# S140032_EMS_10HP_DS.net
KiCad netlist of a schematic drawn in EAGLE
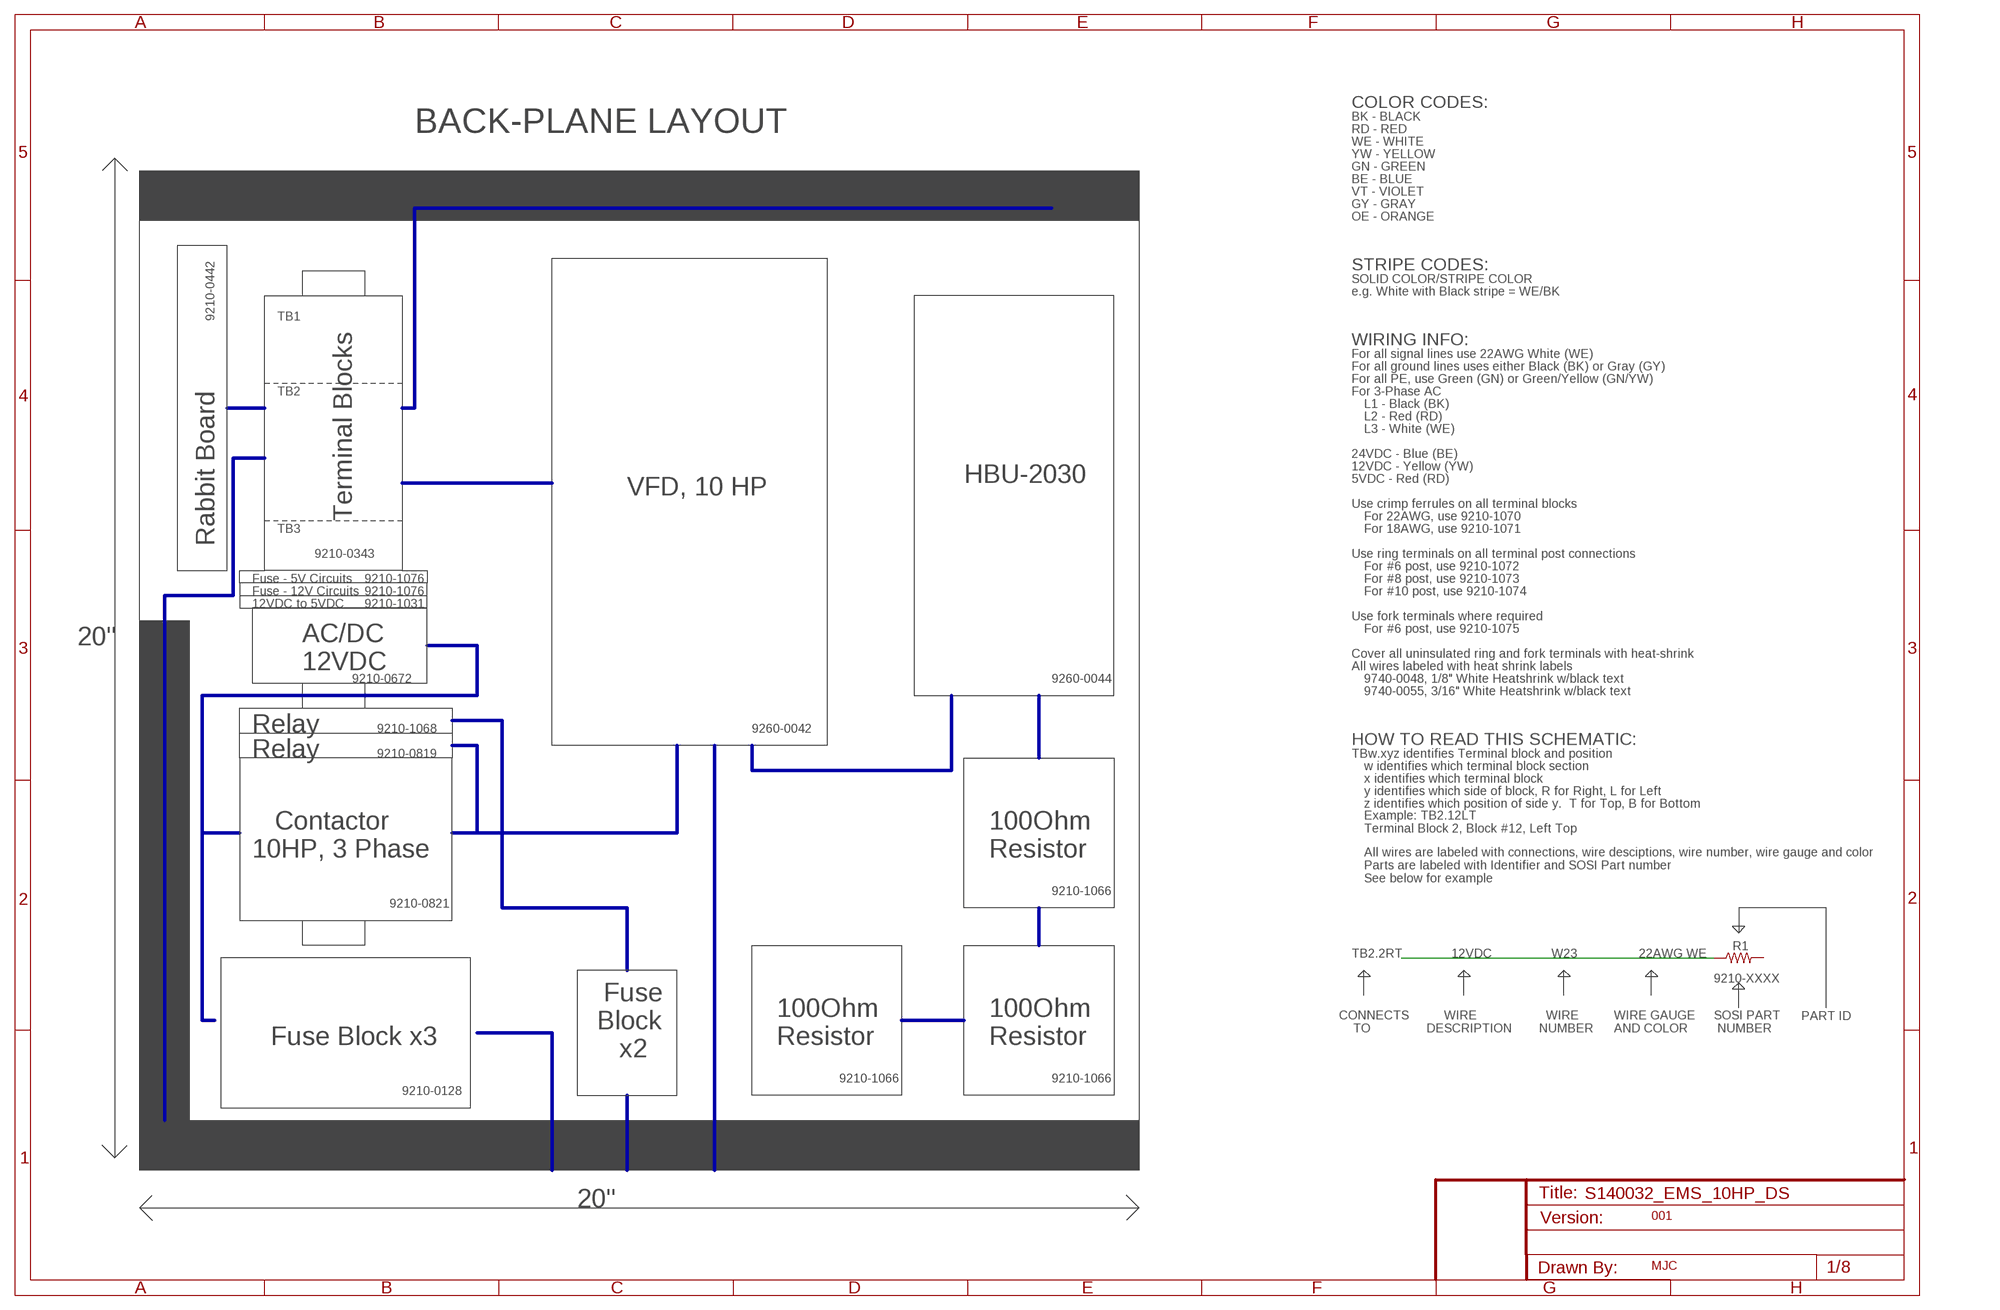
[diagram p0: schematic, sheet 1]
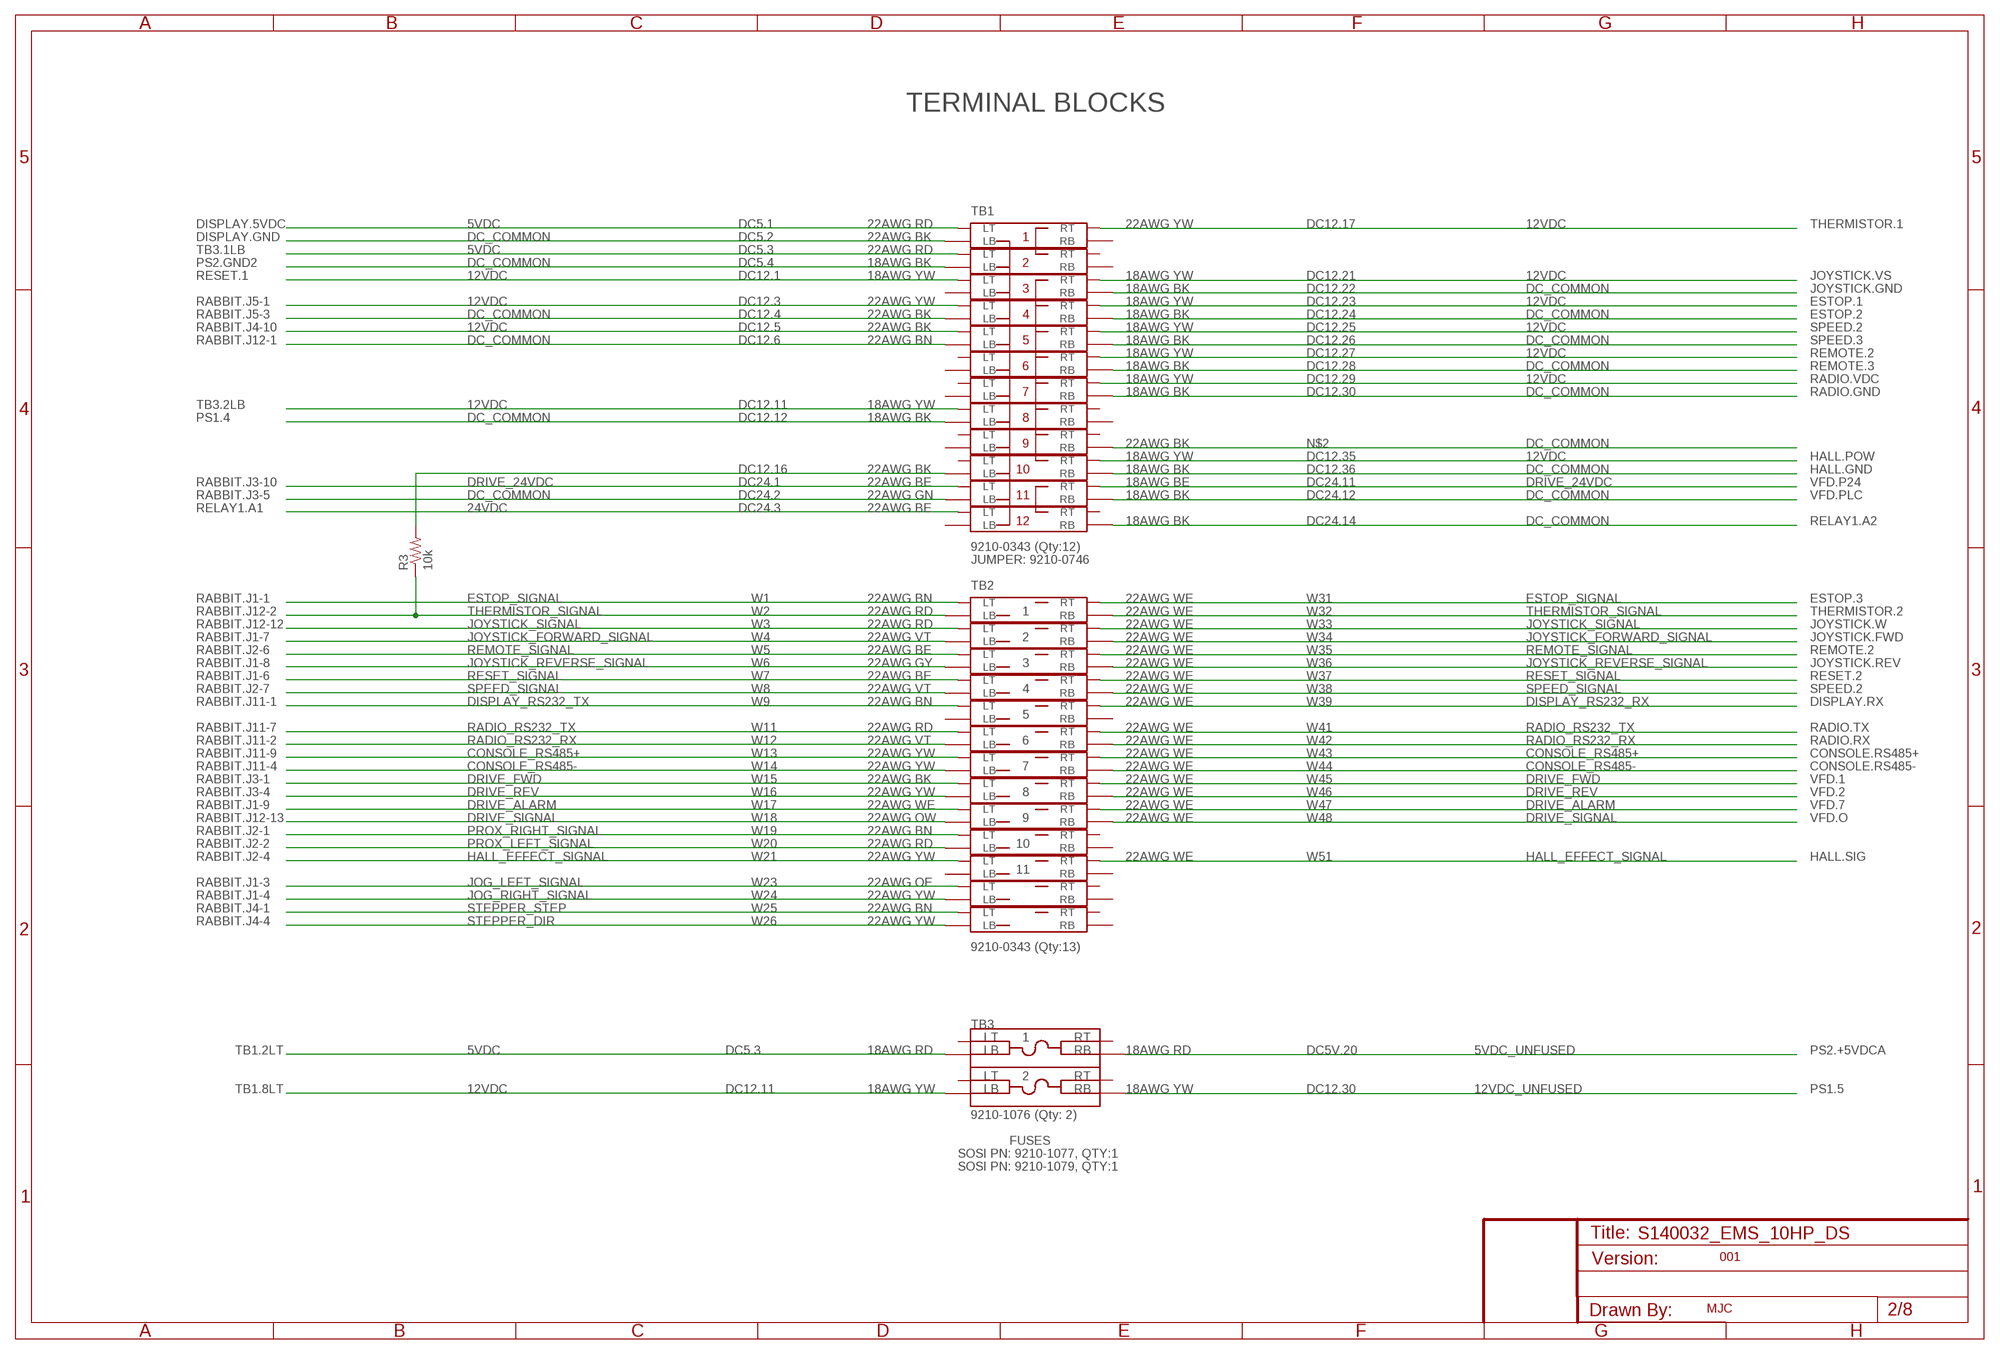
[diagram p1: schematic, sheet 2]
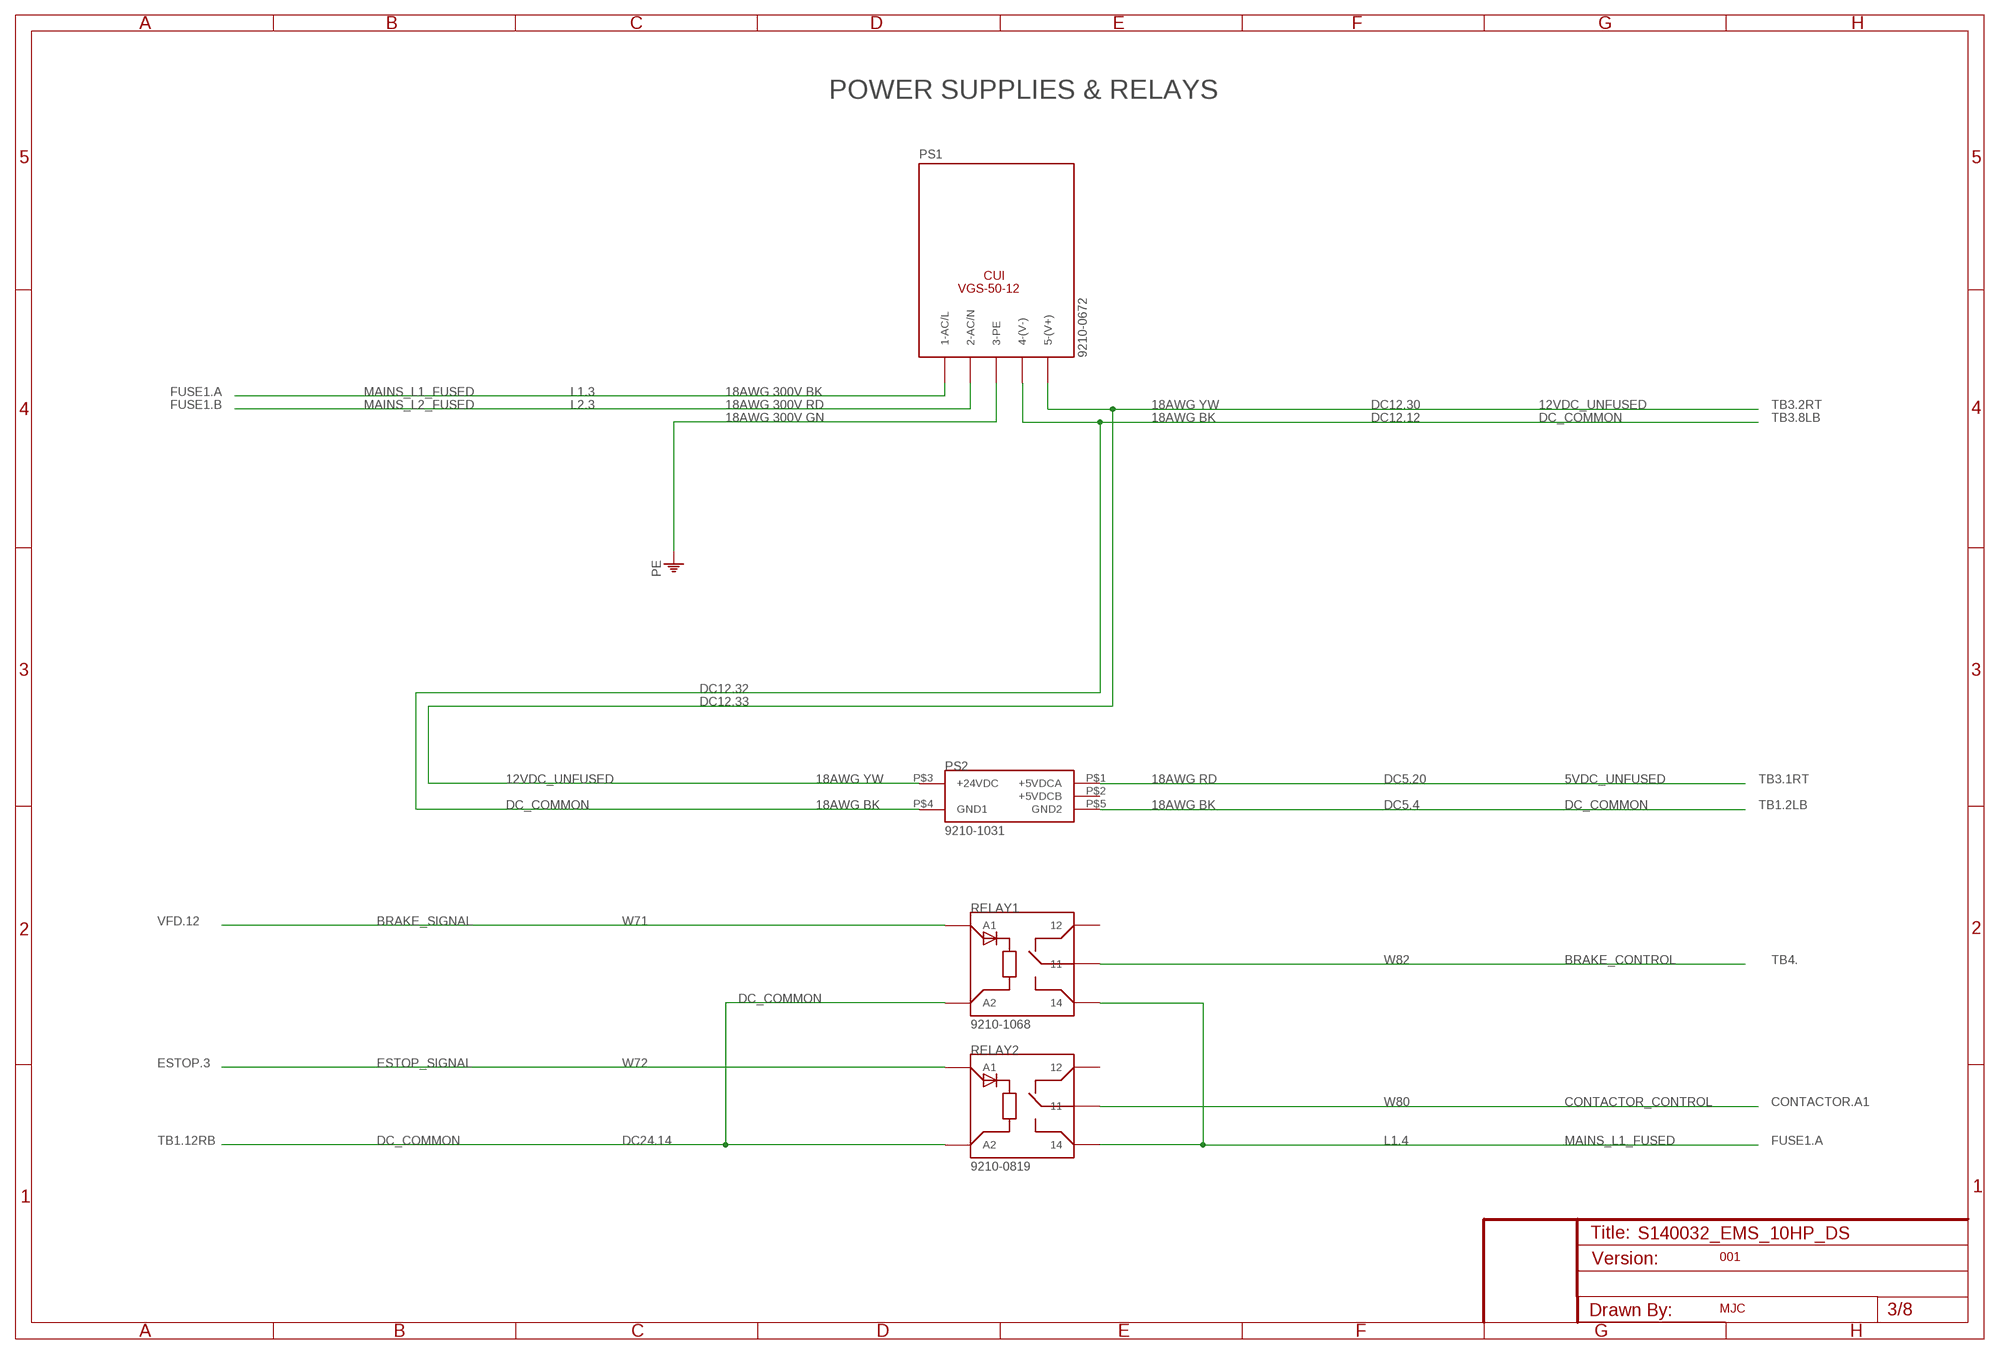
[diagram p2: schematic, sheet 3]
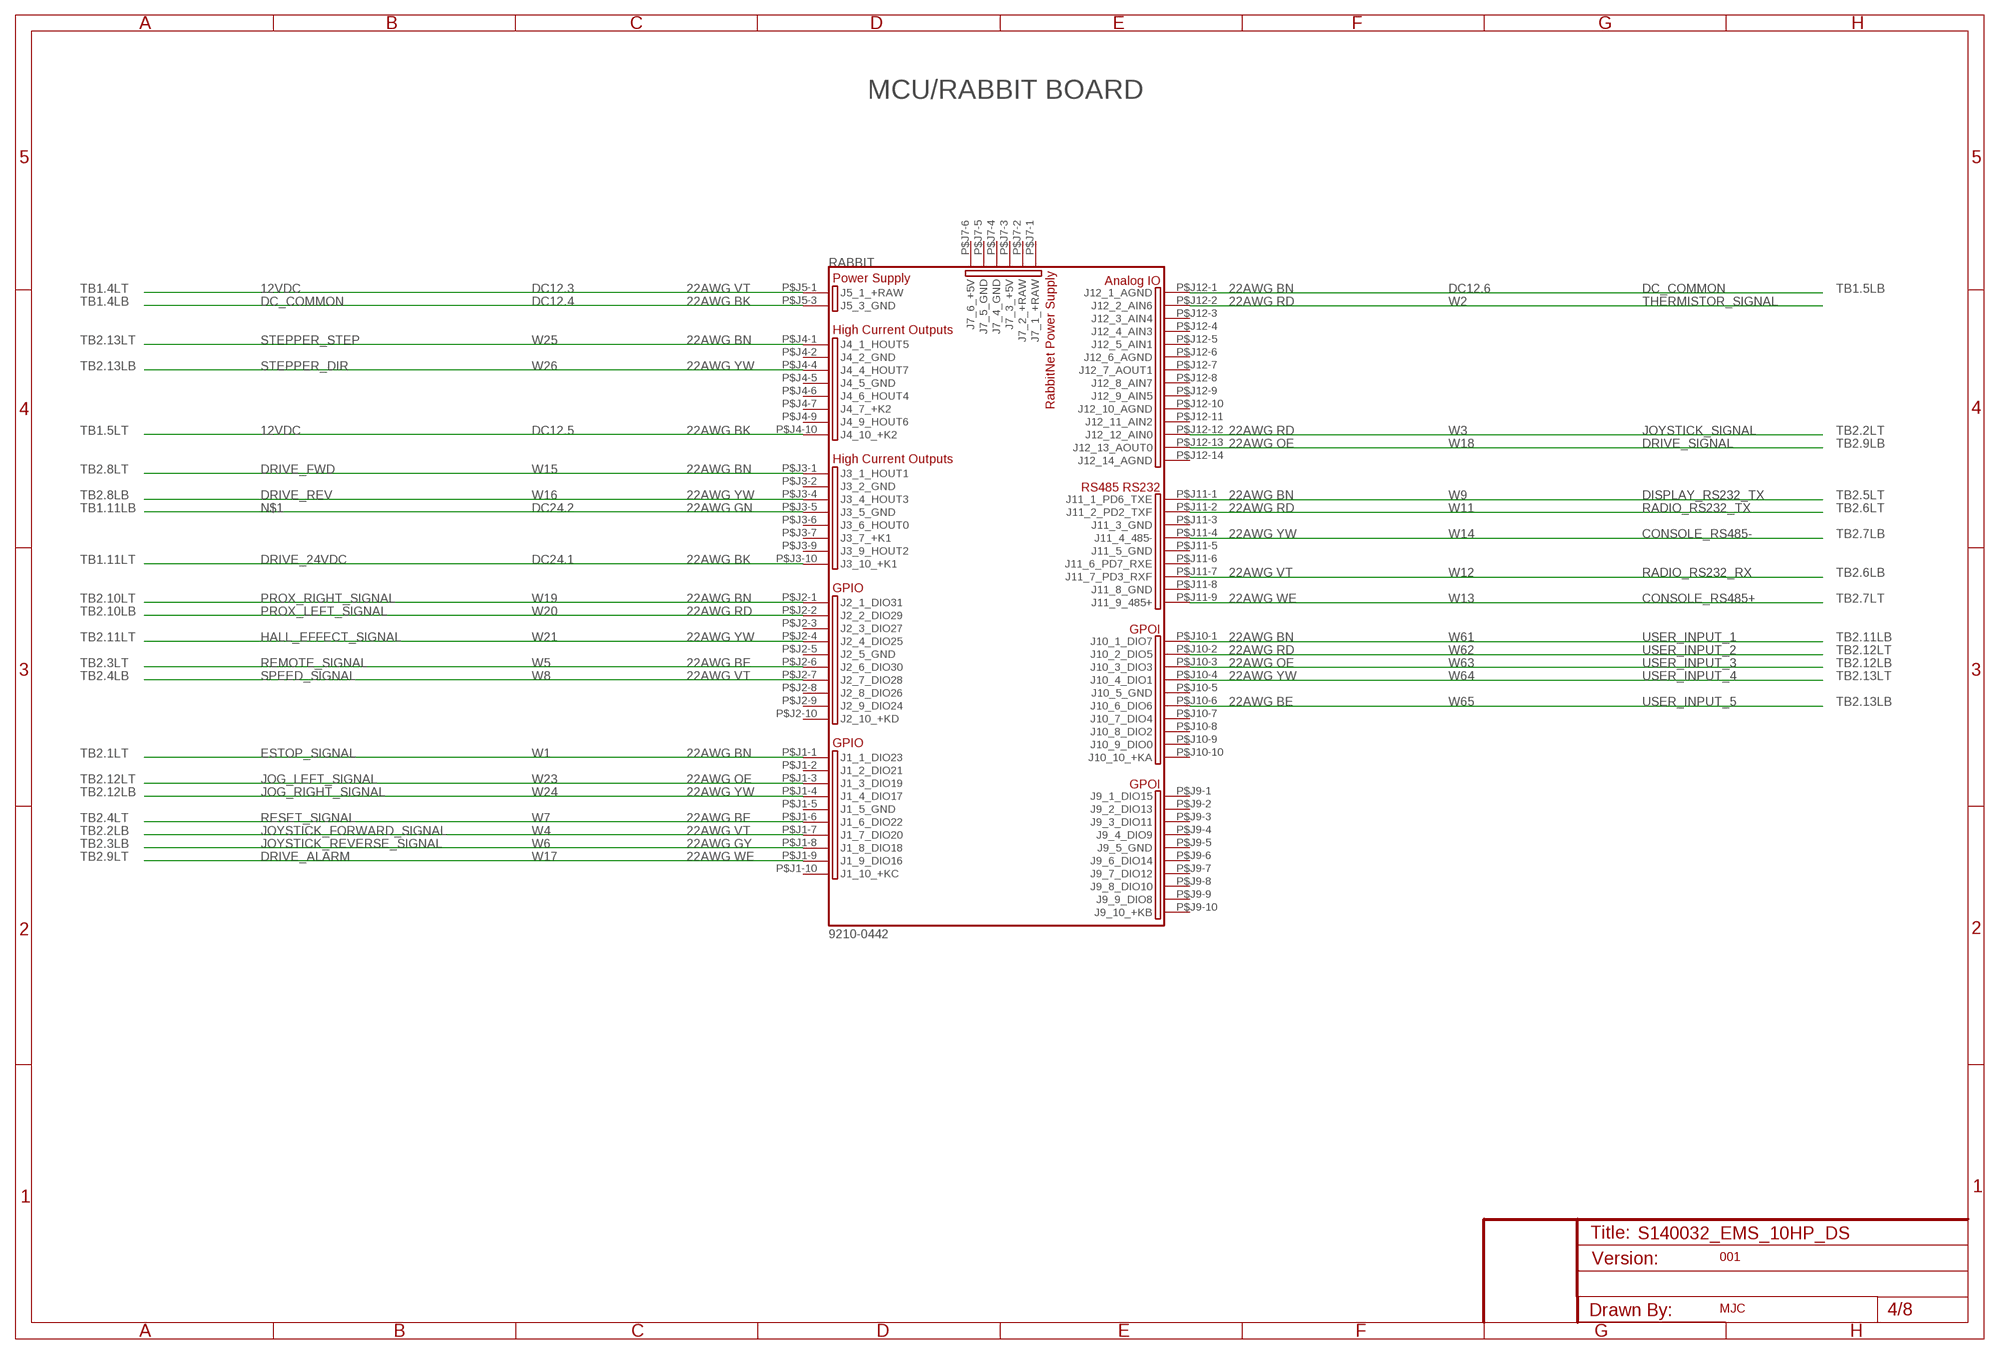
[diagram p3: schematic, sheet 4]
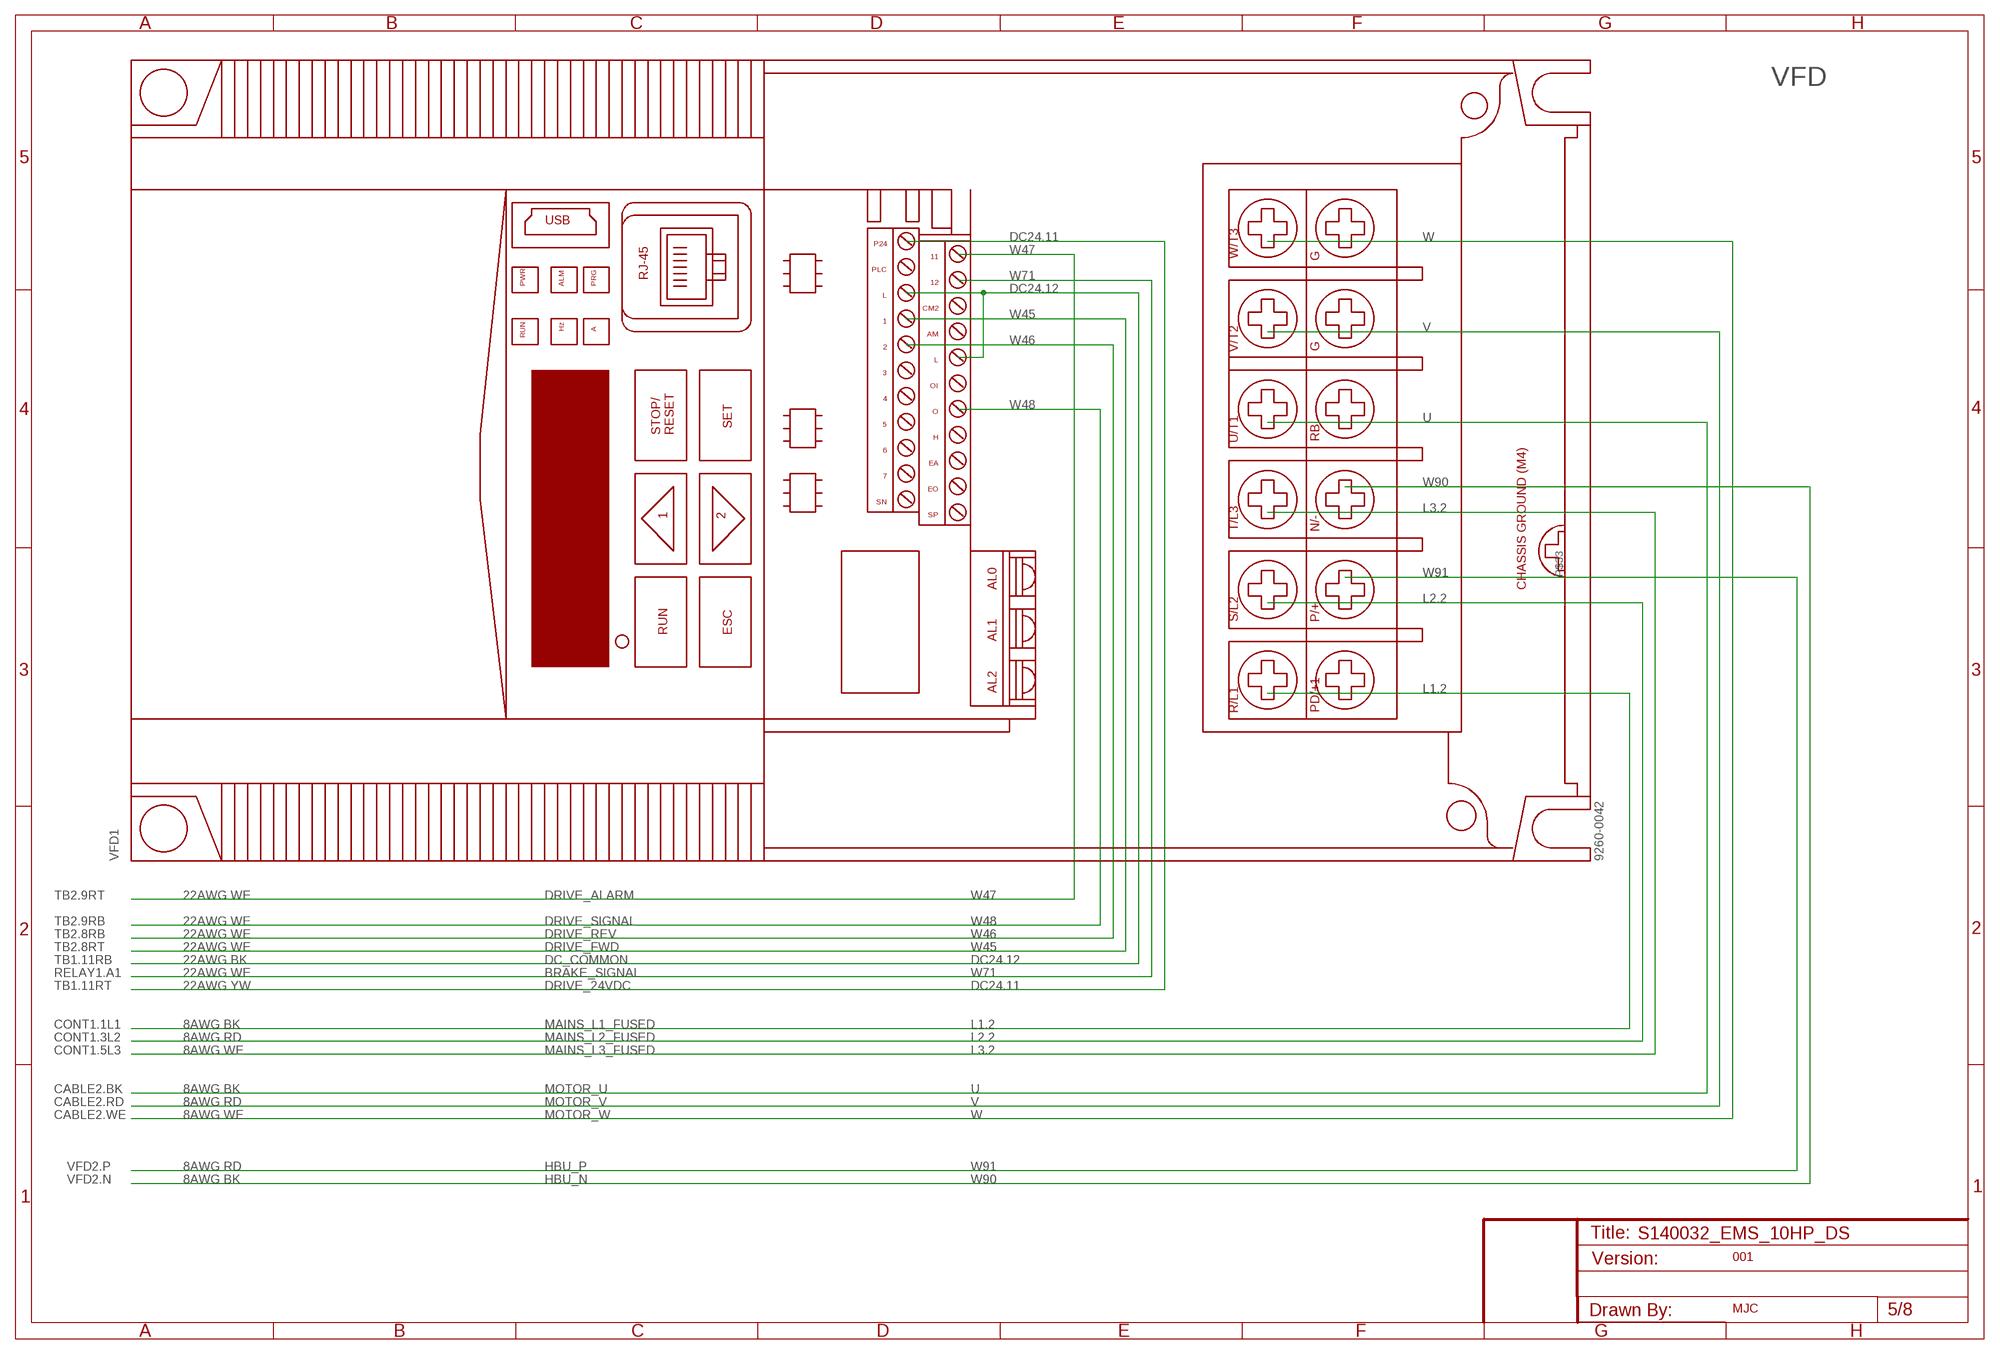
[diagram p4: schematic, sheet 5]
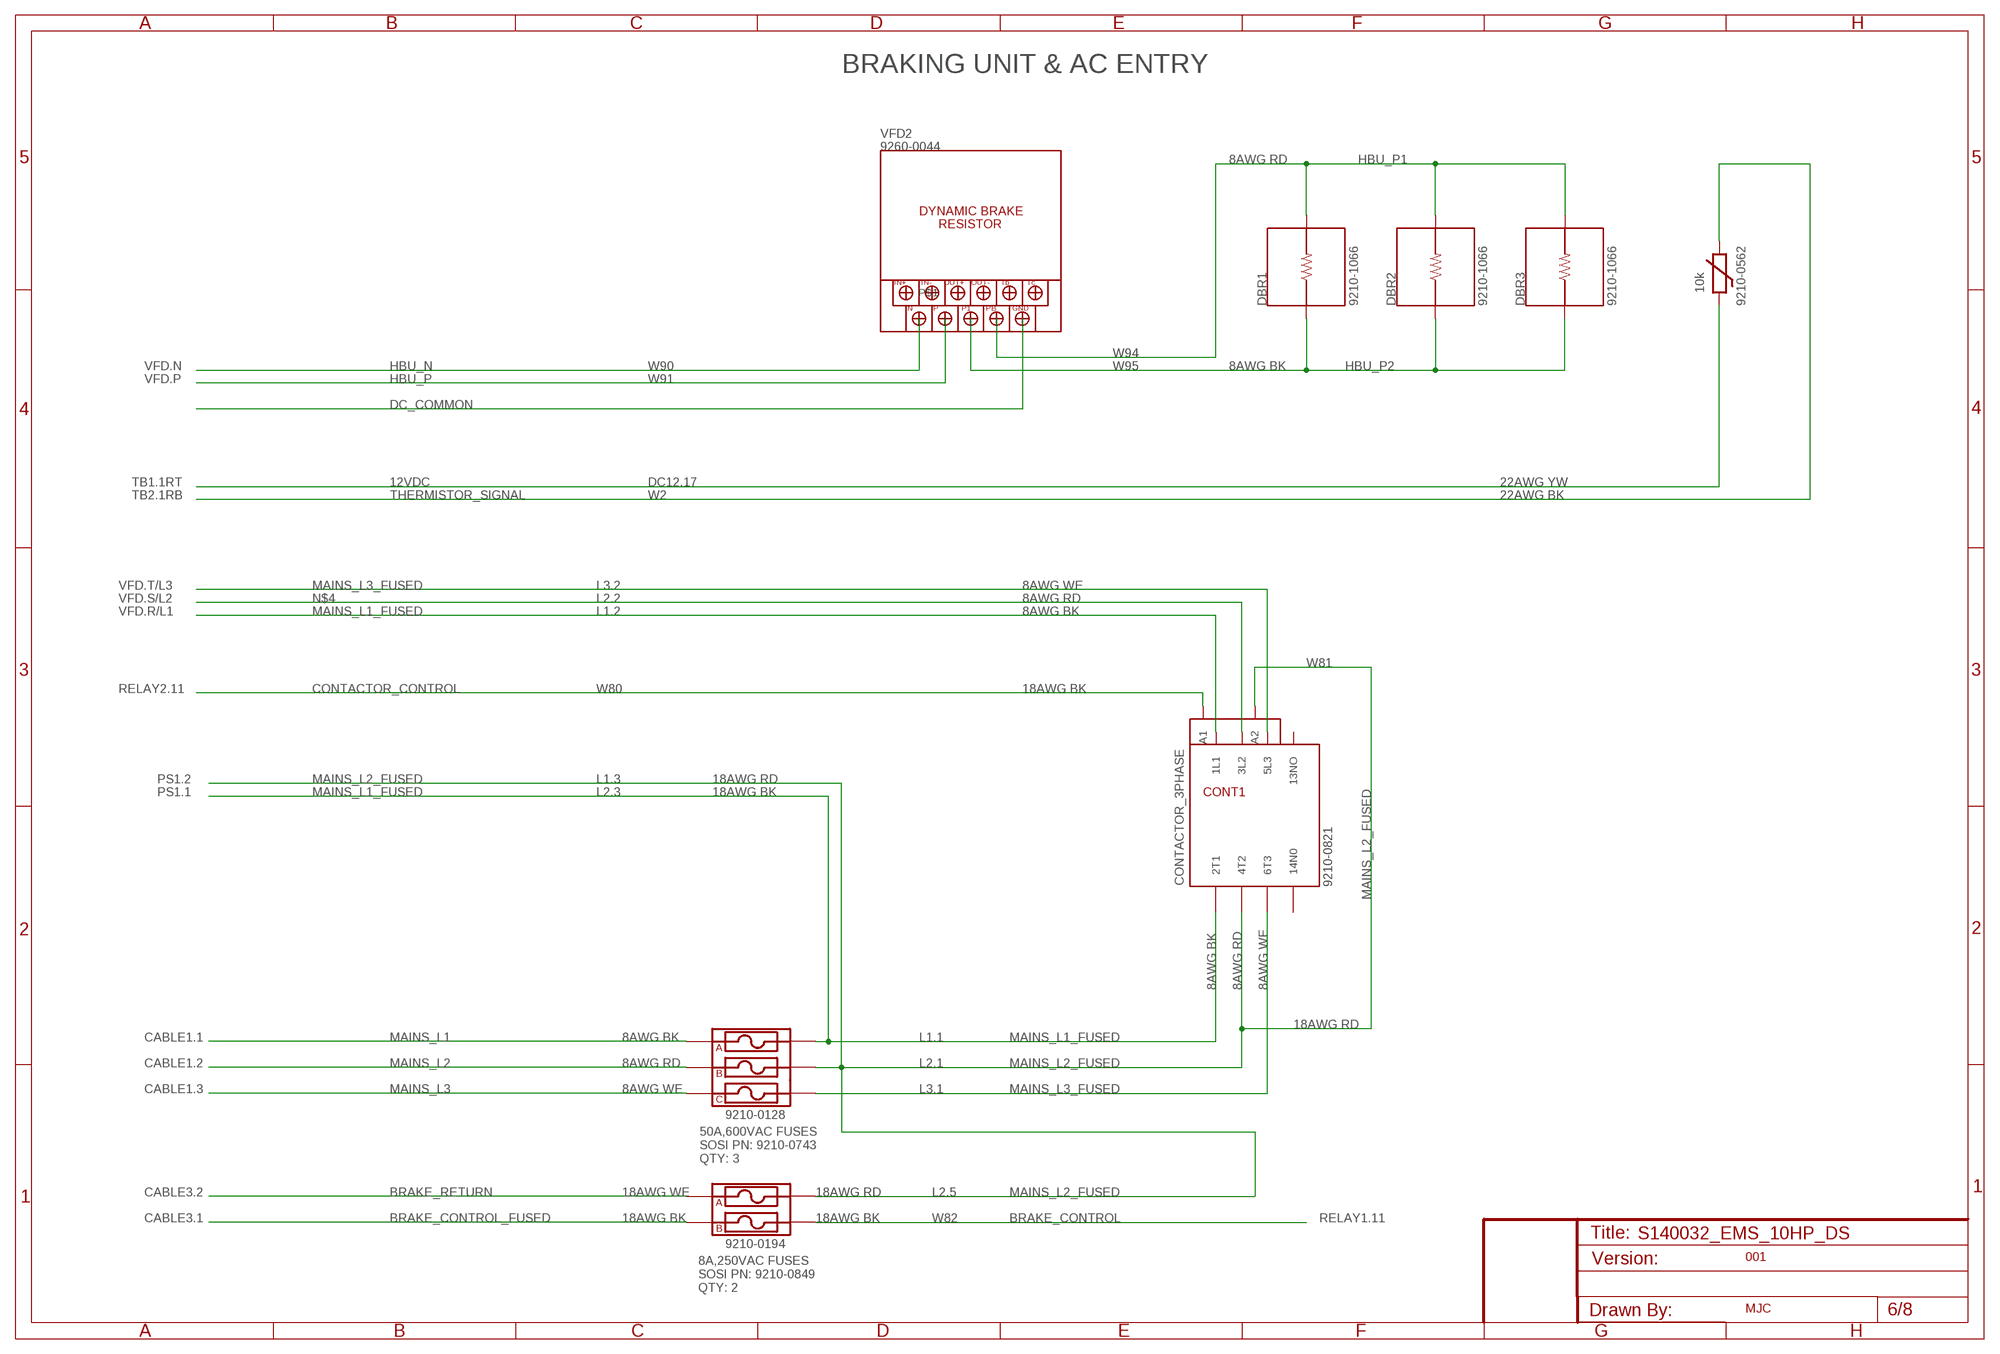
[diagram p5: schematic, sheet 6]
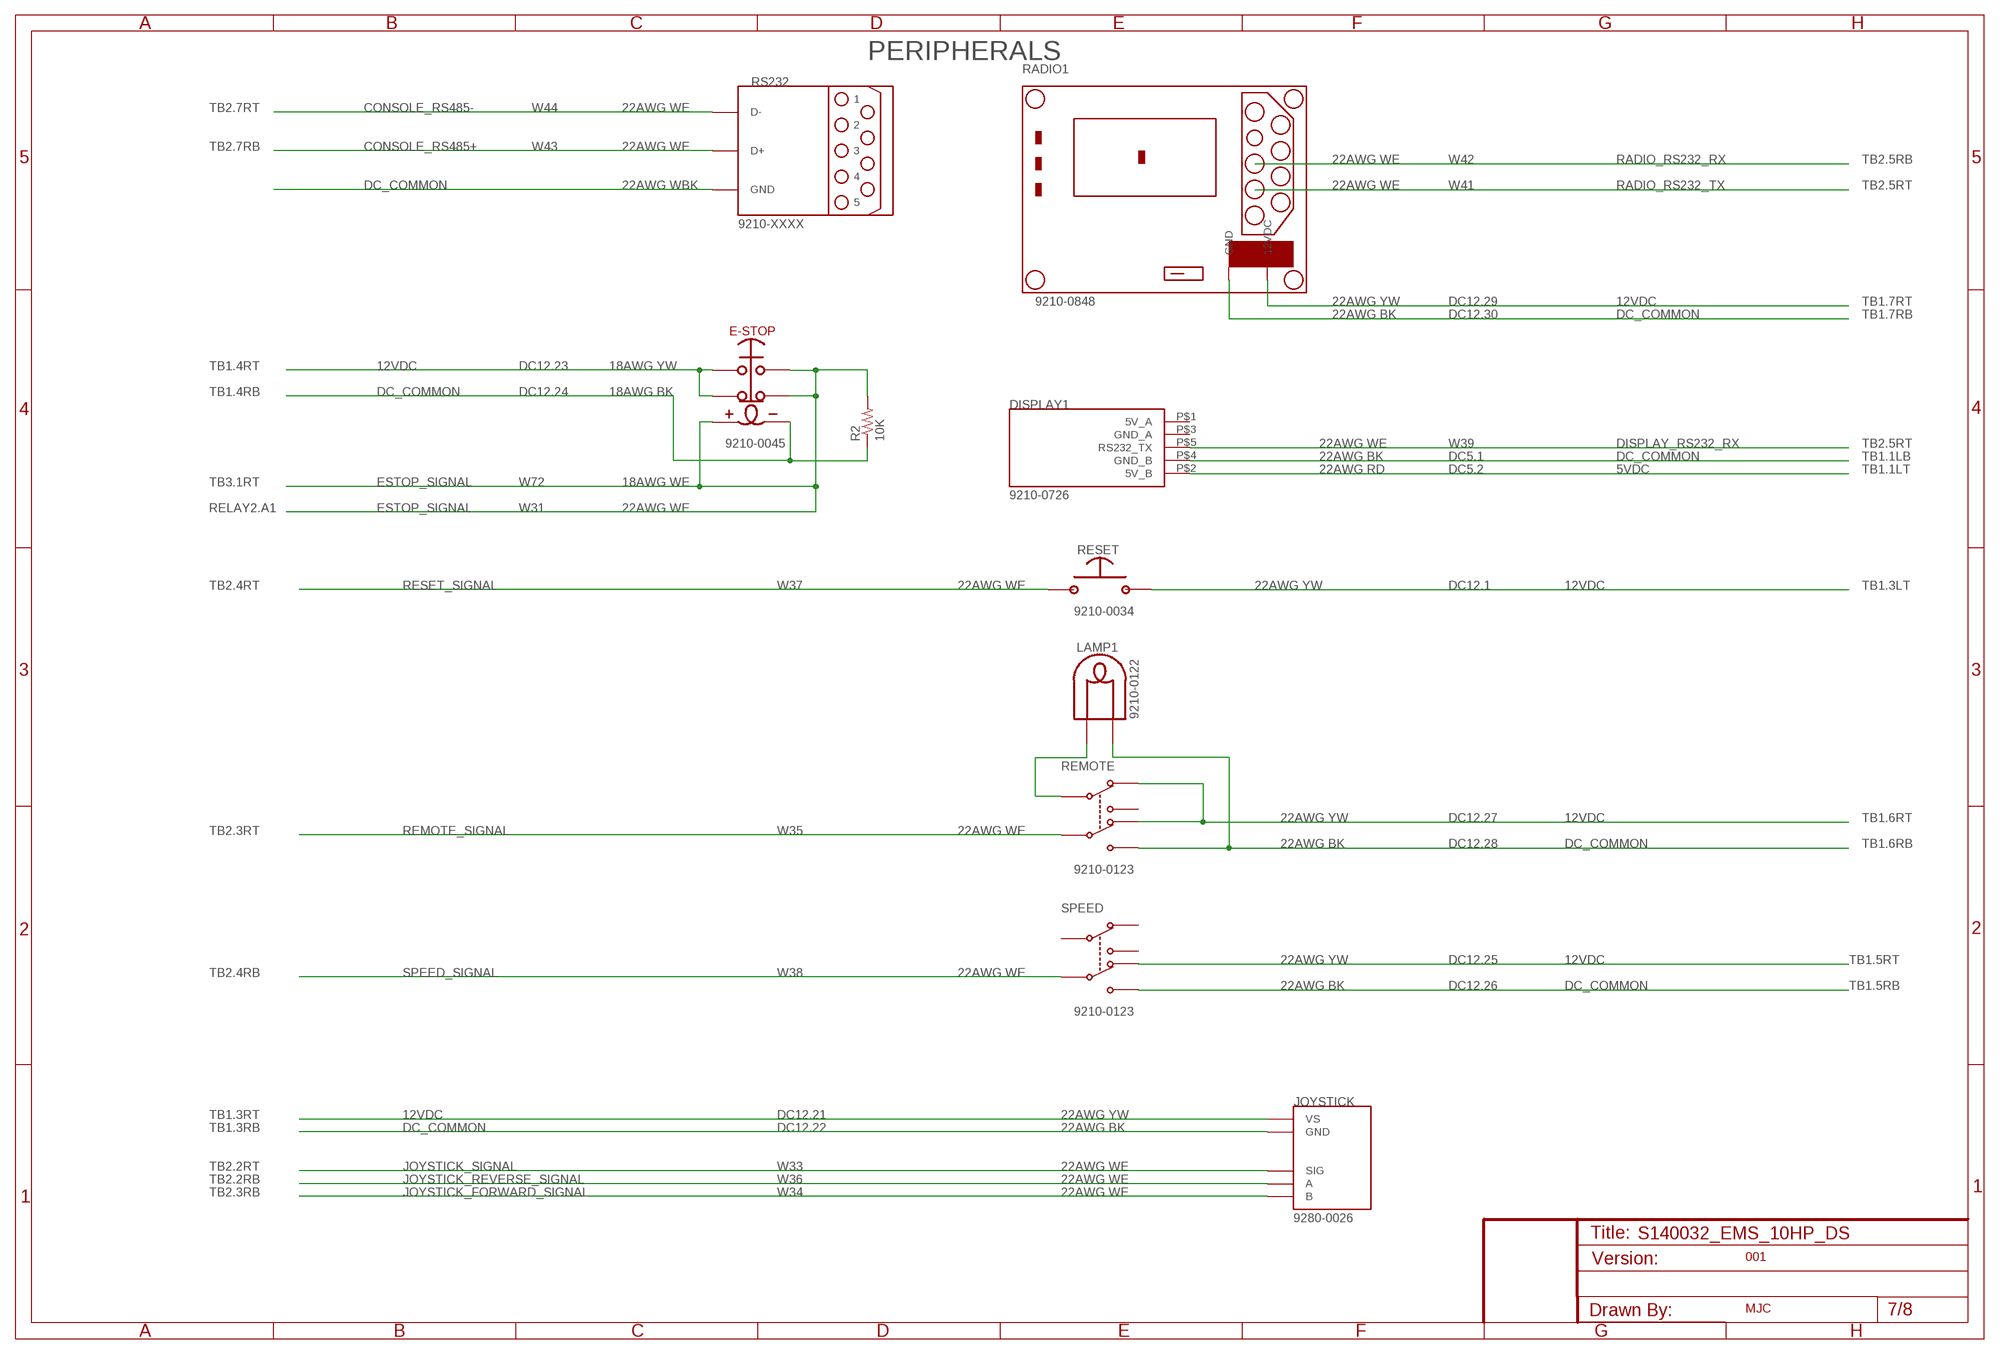
[diagram p6: schematic, sheet 7]
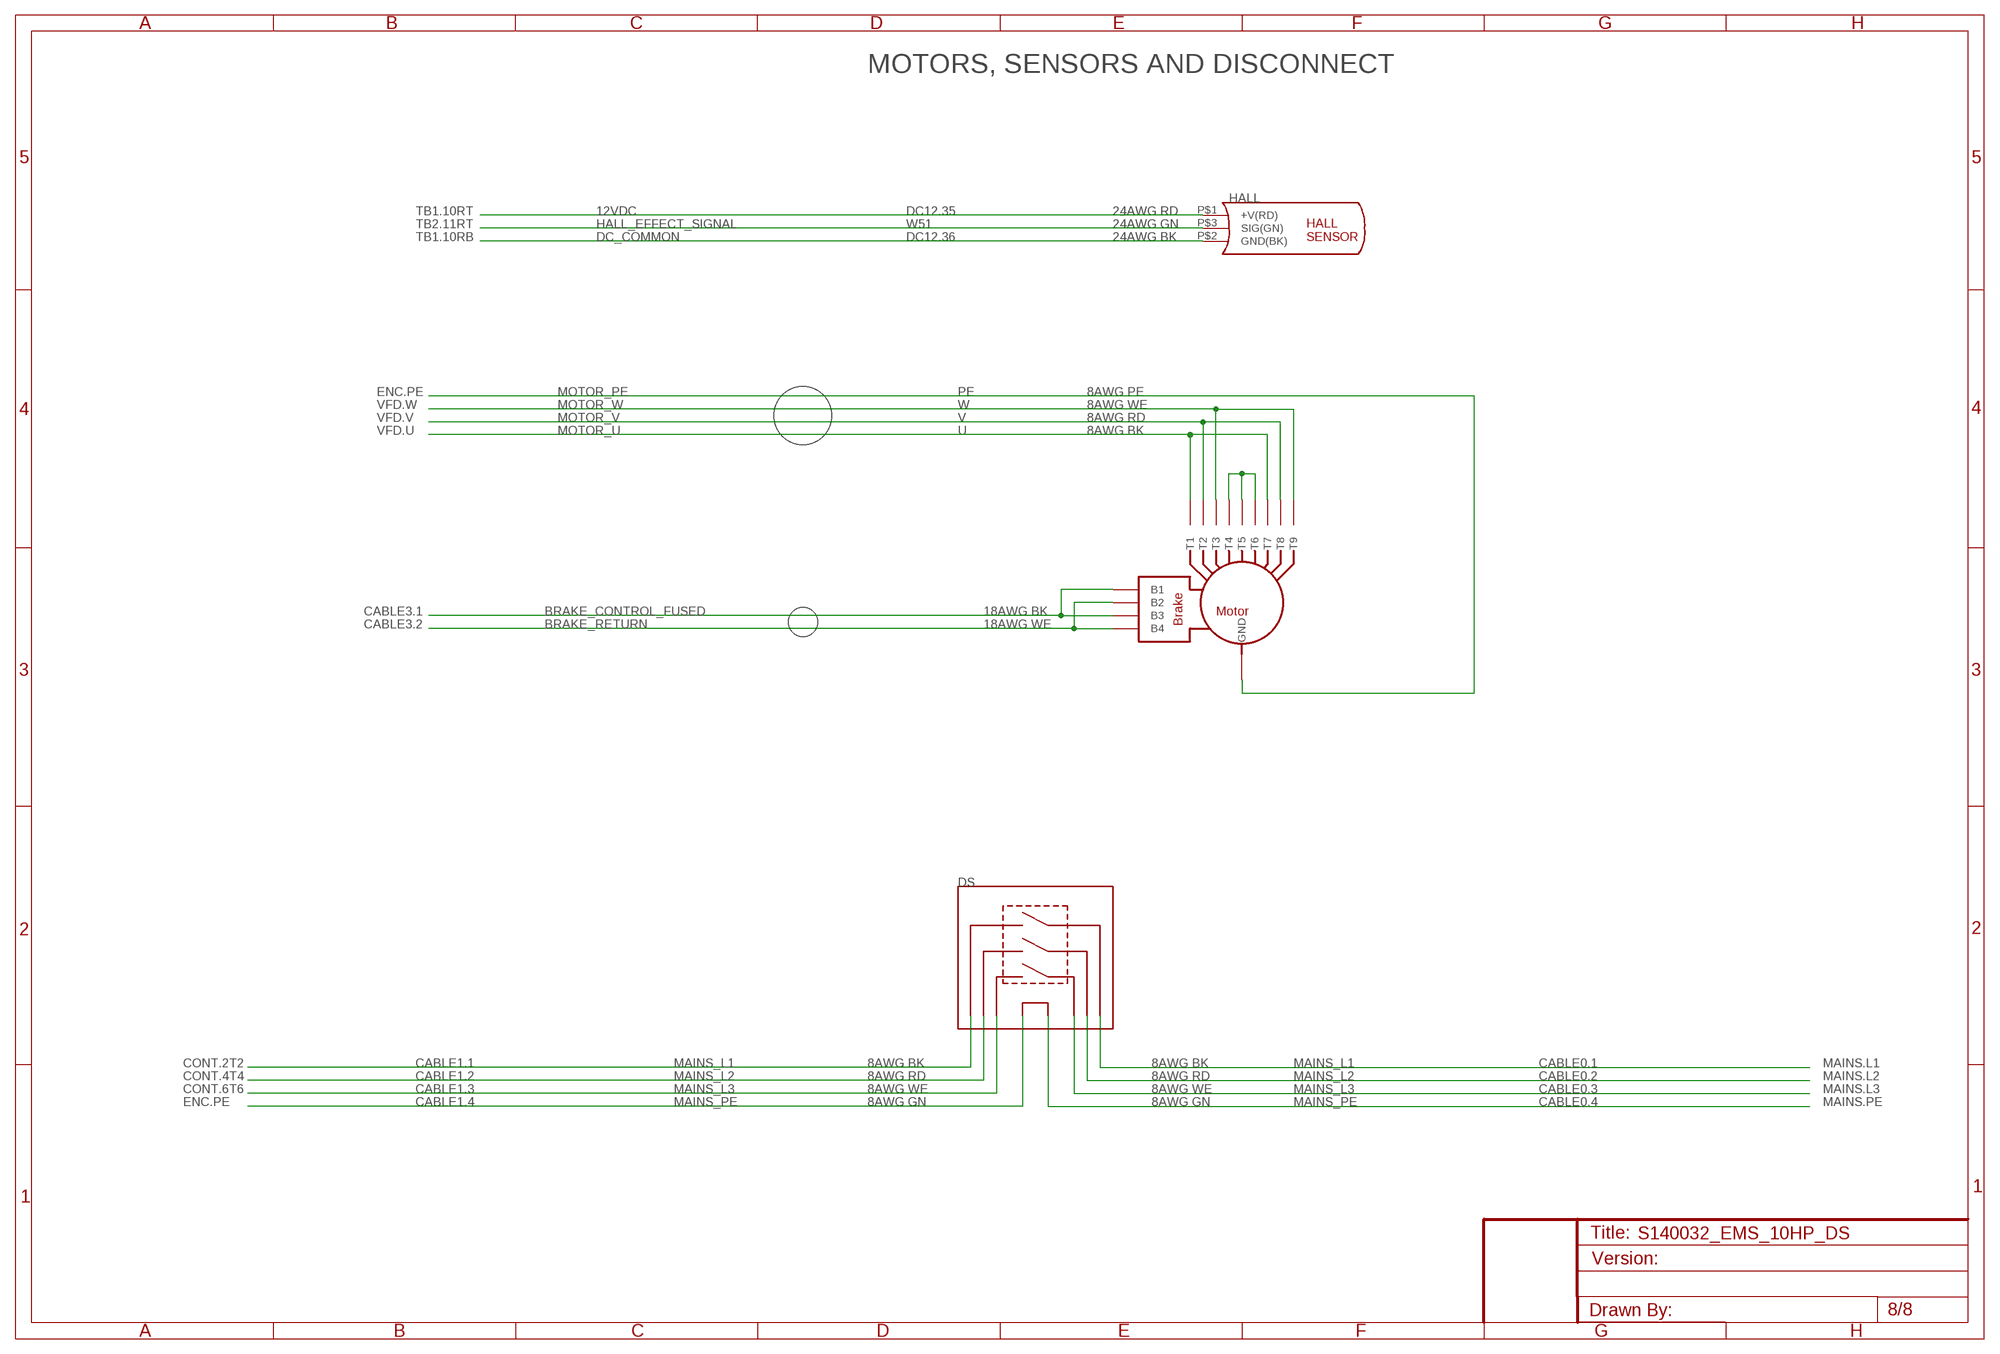
[diagram p7: schematic, sheet 8]

(export (version "E")
  (design (tool "Eeschema 10.0.6"))
  (components
    (comp (ref "PS1")
      (value "DC-DC_CONVERTER_VGS-50-12")
      (footprint "eagle-import:BOGUS")
      (libsource (lib "eagle-import") (part "DC-DC_CONVERTER_VGS-50-12"))
    )
    (comp (ref "PS2")
      (value "DC-DC_CONVERTER_24V-5V")
      (footprint "eagle-import:BOGUS")
      (libsource (lib "eagle-import") (part "DC-DC_CONVERTER_24V-5V"))
    )
    (comp (ref "RELAY1")
      (value "RELAY_TB")
      (footprint "eagle-import:BOGUS")
      (libsource (lib "eagle-import") (part "RELAY_TB"))
    )
    (comp (ref "RELAY2")
      (value "RELAY_TB")
      (footprint "eagle-import:BOGUS")
      (libsource (lib "eagle-import") (part "RELAY_TB"))
    )
    (comp (ref "DS")
      (value "DISCONNECT_SWITCH")
      (footprint "eagle-import:BOGUS")
      (libsource (lib "eagle-import") (part "DISCONNECT_SWITCH"))
    )
    (comp (ref "HALL")
      (value "DRUM_SENSOR")
      (footprint "eagle-import:BOGUS")
      (libsource (lib "eagle-import") (part "DRUM_SENSOR"))
    )
    (comp (ref "U$11")
      (value "MOTOR_3PH")
      (footprint "eagle-import:BOGUS")
      (libsource (lib "eagle-import") (part "MOTOR_3PH"))
    )
    (comp (ref "CONT1")
      (value "CONTACTOR_3PHASE")
      (footprint "eagle-import:BOGUS")
      (libsource (lib "eagle-import") (part "CONTACTOR_3PHASE"))
    )
    (comp (ref "DBR1")
      (value "100 Ohm")
      (footprint "eagle-import:0204_5")
      (libsource (lib "eagle-import") (part "R-DYNAMIC_BRAKE"))
    )
    (comp (ref "DBR2")
      (value "100 Ohm")
      (footprint "eagle-import:0204_5")
      (libsource (lib "eagle-import") (part "R-DYNAMIC_BRAKE"))
    )
    (comp (ref "DBR3")
      (value "100 Ohm")
      (footprint "eagle-import:0204_5")
      (libsource (lib "eagle-import") (part "R-DYNAMIC_BRAKE"))
    )
    (comp (ref "FUSE1")
      (value "FUSE_HOLDER_3-POLE")
      (footprint "eagle-import:BOGUS")
      (libsource (lib "eagle-import") (part "FUSE_HOLDER_3-POLE"))
    )
    (comp (ref "U$5")
      (value "10k")
      (footprint "eagle-import:BOGUS")
      (libsource (lib "eagle-import") (part "THERMISTOR"))
    )
    (comp (ref "U$6")
      (value "FUSE_HOLDER_2-POLE")
      (footprint "eagle-import:BOGUS")
      (libsource (lib "eagle-import") (part "FUSE_HOLDER_2-POLE"))
    )
    (comp (ref "VFD2")
      (value "HITACHI_HBU-2030")
      (footprint "eagle-import:BOGUS")
      (libsource (lib "eagle-import") (part "HITACHI_HBU-2030"))
    )
    (comp (ref "DISPLAY1")
      (value "SEETRON_GLO-416")
      (footprint "eagle-import:BOGUS")
      (libsource (lib "eagle-import") (part "SEETRON_GLO-416"))
    )
    (comp (ref "JOYSTICK")
      (value "JOYSTICK")
      (footprint "eagle-import:BOGUS")
      (libsource (lib "eagle-import") (part "JOYSTICK"))
    )
    (comp (ref "LAMP1")
      (value "INDICATOR_LIGHT")
      (footprint "eagle-import:BOGUS")
      (libsource (lib "eagle-import") (part "INDICATOR_LIGHT"))
    )
    (comp (ref "R2")
      (value "10K")
      (footprint "eagle-import:AXIAL-0.3")
      (libsource (lib "eagle-import") (part "RESISTORAXIAL-0.3"))
    )
    (comp (ref "RADIO1")
      (value "SPARKFUN_XBEE_EXPLORER_SERIAL")
      (footprint "eagle-import:BOGUS")
      (libsource (lib "eagle-import") (part "SPARKFUN_XBEE_EXPLORER_SERIAL"))
    )
    (comp (ref "REMOTE")
      (value "SWITCH_DPDT")
      (footprint "eagle-import:BOGUS")
      (libsource (lib "eagle-import") (part "SWITCH_DPDT"))
    )
    (comp (ref "RESET")
      (value "SWITCH_MOM_NO")
      (footprint "eagle-import:BOGUS")
      (libsource (lib "eagle-import") (part "SWITCH_MOM_NO"))
    )
    (comp (ref "RS232")
      (value "RS232-RS485_CONVERTER")
      (footprint "eagle-import:BOGUS")
      (libsource (lib "eagle-import") (part "RS232-RS485_CONVERTER"))
    )
    (comp (ref "SPEED")
      (value "SWITCH_DPDT")
      (footprint "eagle-import:BOGUS")
      (libsource (lib "eagle-import") (part "SWITCH_DPDT"))
    )
    (comp (ref "U$3")
      (value "SWITCH_ESTOP_LIGHTED")
      (footprint "eagle-import:BOGUS")
      (libsource (lib "eagle-import") (part "SWITCH_ESTOP_LIGHTED"))
    )
    (comp (ref "VFD1")
      (value "HITACHI_WJ200-075LF")
      (footprint "eagle-import:BOGUS")
      (libsource (lib "eagle-import") (part "HITACHI_WJ200-075LF"))
    )
    (comp (ref "CPU1")
      (value "RABBIT_BL4S200(RCM4310)")
      (footprint "eagle-import:RABBIT_BL4S200")
      (libsource (lib "eagle-import") (part "RABBIT_BL4S200(RCM4310)"))
    )
    (comp (ref "R3")
      (value "10k")
      (footprint "eagle-import:0204V")
      (libsource (lib "eagle-import") (part "R-US_0204/2V"))
    )
    (comp (ref "U$1")
      (value "TB_3031160_1POS")
      (footprint "eagle-import:BOGUS")
      (libsource (lib "eagle-import") (part "TB_3031160_1POS"))
    )
    (comp (ref "U$2")
      (value "TB_3031160_1POS")
      (footprint "eagle-import:BOGUS")
      (libsource (lib "eagle-import") (part "TB_3031160_1POS"))
    )
    (comp (ref "U$4")
      (value "TB_3031160_1POS")
      (footprint "eagle-import:BOGUS")
      (libsource (lib "eagle-import") (part "TB_3031160_1POS"))
    )
    (comp (ref "U$7")
      (value "TB_3031160_1POS")
      (footprint "eagle-import:BOGUS")
      (libsource (lib "eagle-import") (part "TB_3031160_1POS"))
    )
    (comp (ref "U$8")
      (value "TB_3031160_1POS")
      (footprint "eagle-import:BOGUS")
      (libsource (lib "eagle-import") (part "TB_3031160_1POS"))
    )
    (comp (ref "U$9")
      (value "TB_FUSE_DDFL4ULR")
      (footprint "eagle-import:BOGUS")
      (libsource (lib "eagle-import") (part "TB_FUSE_DDFL4ULR"))
    )
    (comp (ref "U$10")
      (value "TB_FUSE_DDFL4ULR")
      (footprint "eagle-import:BOGUS")
      (libsource (lib "eagle-import") (part "TB_FUSE_DDFL4ULR"))
    )
    (comp (ref "U$16")
      (value "TB_3031160_1POS")
      (footprint "eagle-import:BOGUS")
      (libsource (lib "eagle-import") (part "TB_3031160_1POS"))
    )
    (comp (ref "U$17")
      (value "TB_3031160_1POS")
      (footprint "eagle-import:BOGUS")
      (libsource (lib "eagle-import") (part "TB_3031160_1POS"))
    )
    (comp (ref "U$18")
      (value "TB_3031160_1POS")
      (footprint "eagle-import:BOGUS")
      (libsource (lib "eagle-import") (part "TB_3031160_1POS"))
    )
    (comp (ref "U$19")
      (value "TB_3031160_1POS")
      (footprint "eagle-import:BOGUS")
      (libsource (lib "eagle-import") (part "TB_3031160_1POS"))
    )
    (comp (ref "U$20")
      (value "TB_3031160_1POS")
      (footprint "eagle-import:BOGUS")
      (libsource (lib "eagle-import") (part "TB_3031160_1POS"))
    )
    (comp (ref "U$21")
      (value "TB_3031160_1POS")
      (footprint "eagle-import:BOGUS")
      (libsource (lib "eagle-import") (part "TB_3031160_1POS"))
    )
    (comp (ref "U$22")
      (value "TB_3031160_1POS")
      (footprint "eagle-import:BOGUS")
      (libsource (lib "eagle-import") (part "TB_3031160_1POS"))
    )
    (comp (ref "U$23")
      (value "TB_3031160_1POS")
      (footprint "eagle-import:BOGUS")
      (libsource (lib "eagle-import") (part "TB_3031160_1POS"))
    )
    (comp (ref "U$24")
      (value "TB_3031160_1POS")
      (footprint "eagle-import:BOGUS")
      (libsource (lib "eagle-import") (part "TB_3031160_1POS"))
    )
    (comp (ref "U$25")
      (value "TB_3031160_1POS")
      (footprint "eagle-import:BOGUS")
      (libsource (lib "eagle-import") (part "TB_3031160_1POS"))
    )
    (comp (ref "U$26")
      (value "TB_3031160_1POS")
      (footprint "eagle-import:BOGUS")
      (libsource (lib "eagle-import") (part "TB_3031160_1POS"))
    )
    (comp (ref "U$27")
      (value "TB_3031160_1POS")
      (footprint "eagle-import:BOGUS")
      (libsource (lib "eagle-import") (part "TB_3031160_1POS"))
    )
    (comp (ref "U$28")
      (value "TB_3031160_1POS")
      (footprint "eagle-import:BOGUS")
      (libsource (lib "eagle-import") (part "TB_3031160_1POS"))
    )
    (comp (ref "U$29")
      (value "TB_3031160_1POS")
      (footprint "eagle-import:BOGUS")
      (libsource (lib "eagle-import") (part "TB_3031160_1POS"))
    )
    (comp (ref "U$30")
      (value "TB_3031160_1POS")
      (footprint "eagle-import:BOGUS")
      (libsource (lib "eagle-import") (part "TB_3031160_1POS"))
    )
    (comp (ref "U$31")
      (value "TB_3031160_1POS")
      (footprint "eagle-import:BOGUS")
      (libsource (lib "eagle-import") (part "TB_3031160_1POS"))
    )
    (comp (ref "U$32")
      (value "TB_3031160_1POS")
      (footprint "eagle-import:BOGUS")
      (libsource (lib "eagle-import") (part "TB_3031160_1POS"))
    )
    (comp (ref "U$33")
      (value "TB_3031160_1POS")
      (footprint "eagle-import:BOGUS")
      (libsource (lib "eagle-import") (part "TB_3031160_1POS"))
    )
    (comp (ref "U$34")
      (value "TB_3031160_1POS")
      (footprint "eagle-import:BOGUS")
      (libsource (lib "eagle-import") (part "TB_3031160_1POS"))
    )
    (comp (ref "U$35")
      (value "TB_3031160_1POS")
      (footprint "eagle-import:BOGUS")
      (libsource (lib "eagle-import") (part "TB_3031160_1POS"))
    )
    (comp (ref "R1")
      (value "R-US_0204/2V")
      (footprint "eagle-import:0204V")
      (libsource (lib "eagle-import") (part "R-US_0204/2V"))
    )
  )
  (nets
    (net (code "1") (name "5VDC") (class "Default")
      (node (ref "DISPLAY1") (pin "P$2") (pinfunction "5V_B_P$2") (pintype "bidirectional"))
      (node (ref "U$34") (pin "P$2") (pinfunction "LT_P$2") (pintype "bidirectional"))
      (node (ref "U$35") (pin "P$2") (pinfunction "LT_P$2") (pintype "bidirectional"))
      (node (ref "U$9") (pin "P$2") (pinfunction "P$2_P$2") (pintype "bidirectional"))
    )
    (net (code "2") (name "5VDC_UNFUSED") (class "Default")
      (node (ref "PS2") (pin "P$1") (pinfunction "+5VDCA_P$1") (pintype "bidirectional"))
      (node (ref "U$9") (pin "P$4") (pinfunction "P$4_P$4") (pintype "bidirectional"))
    )
    (net (code "3") (name "12VDC") (class "Default")
      (node (ref "CPU1") (pin "P$J4-10") (pinfunction "J4_10_+K2_P$J4-10") (pintype "bidirectional"))
      (node (ref "CPU1") (pin "P$J5-1") (pinfunction "J5_1_+RAW_P$J5-1") (pintype "bidirectional"))
      (node (ref "HALL") (pin "P$1") (pinfunction "+V(RD)_P$1") (pintype "bidirectional"))
      (node (ref "JOYSTICK") (pin "P$5") (pinfunction "VS_P$5") (pintype "bidirectional"))
      (node (ref "R1") (pin "1") (pinfunction "1_1") (pintype "passive"))
      (node (ref "RADIO1") (pin "P$52") (pinfunction "12VDC_P$52") (pintype "bidirectional"))
      (node (ref "REMOTE") (pin "P$2") (pinfunction "P$2_P$2") (pintype "bidirectional"))
      (node (ref "REMOTE") (pin "P$5") (pinfunction "P$5_P$5") (pintype "bidirectional"))
      (node (ref "RESET") (pin "P$2") (pinfunction "P$2_P$2") (pintype "bidirectional"))
      (node (ref "SPEED") (pin "P$5") (pinfunction "P$5_P$5") (pintype "bidirectional"))
      (node (ref "U$10") (pin "P$2") (pinfunction "P$2_P$2") (pintype "bidirectional"))
      (node (ref "U$28") (pin "P$2") (pinfunction "LT_P$2") (pintype "bidirectional"))
      (node (ref "U$29") (pin "P$4") (pinfunction "RT_P$4") (pintype "bidirectional"))
      (node (ref "U$3") (pin "P$1") (pinfunction "P$1_P$1") (pintype "bidirectional"))
      (node (ref "U$3") (pin "P$2") (pinfunction "P$2_P$2") (pintype "bidirectional"))
      (node (ref "U$30") (pin "P$4") (pinfunction "RT_P$4") (pintype "bidirectional"))
      (node (ref "U$31") (pin "P$2") (pinfunction "LT_P$2") (pintype "bidirectional"))
      (node (ref "U$31") (pin "P$4") (pinfunction "RT_P$4") (pintype "bidirectional"))
      (node (ref "U$32") (pin "P$2") (pinfunction "LT_P$2") (pintype "bidirectional"))
      (node (ref "U$32") (pin "P$4") (pinfunction "RT_P$4") (pintype "bidirectional"))
      (node (ref "U$33") (pin "P$2") (pinfunction "LT_P$2") (pintype "bidirectional"))
      (node (ref "U$33") (pin "P$4") (pinfunction "RT_P$4") (pintype "bidirectional"))
      (node (ref "U$35") (pin "P$4") (pinfunction "RT_P$4") (pintype "bidirectional"))
      (node (ref "U$5") (pin "P$2") (pinfunction "P$2_P$2") (pintype "bidirectional"))
      (node (ref "U$8") (pin "P$4") (pinfunction "RT_P$4") (pintype "bidirectional"))
    )
    (net (code "4") (name "12VDC_UNFUSED") (class "Default")
      (node (ref "PS1") (pin "P$5") (pinfunction "5-(V+)_P$5") (pintype "bidirectional"))
      (node (ref "PS2") (pin "P$3") (pinfunction "+24VDC_P$3") (pintype "bidirectional"))
      (node (ref "U$10") (pin "P$4") (pinfunction "P$4_P$4") (pintype "bidirectional"))
    )
    (net (code "5") (name "24VDC") (class "Default")
      (node (ref "U$26") (pin "P$2") (pinfunction "LT_P$2") (pintype "bidirectional"))
    )
    (net (code "6") (name "BRAKE_CONTROL") (class "Default")
      (node (ref "RELAY1") (pin "P$1") (pinfunction "11_P$1") (pintype "bidirectional"))
      (node (ref "U$6") (pin "P$4") (pinfunction "P$4_P$4") (pintype "bidirectional"))
    )
    (net (code "7") (name "BRAKE_CONTROL_FUSED") (class "Default")
      (node (ref "U$11") (pin "P$1") (pinfunction "B1_P$1") (pintype "bidirectional"))
      (node (ref "U$11") (pin "P$3") (pinfunction "B3_P$3") (pintype "bidirectional"))
      (node (ref "U$6") (pin "P$1") (pinfunction "P$1_P$1") (pintype "bidirectional"))
    )
    (net (code "8") (name "BRAKE_RETURN") (class "Default")
      (node (ref "U$11") (pin "P$2") (pinfunction "B2_P$2") (pintype "bidirectional"))
      (node (ref "U$11") (pin "P$4") (pinfunction "B4_P$4") (pintype "bidirectional"))
      (node (ref "U$6") (pin "P$2") (pinfunction "P$2_P$2") (pintype "bidirectional"))
    )
    (net (code "9") (name "BRAKE_SIGNAL") (class "Default")
      (node (ref "RELAY1") (pin "P$4") (pinfunction "A1_P$4") (pintype "bidirectional"))
      (node (ref "VFD1") (pin "P$21") (pinfunction "P$21_P$21") (pintype "bidirectional"))
    )
    (net (code "10") (name "CONSOLE_RS485+") (class "Default")
      (node (ref "CPU1") (pin "P$J11-9") (pinfunction "J11_9_485+_P$J11-9") (pintype "bidirectional"))
      (node (ref "RS232") (pin "P$10") (pinfunction "D+_P$10") (pintype "bidirectional"))
      (node (ref "U$21") (pin "P$2") (pinfunction "LT_P$2") (pintype "bidirectional"))
      (node (ref "U$21") (pin "P$4") (pinfunction "RT_P$4") (pintype "bidirectional"))
    )
    (net (code "11") (name "CONSOLE_RS485-") (class "Default")
      (node (ref "CPU1") (pin "P$J11-4") (pinfunction "J11_4_485-_P$J11-4") (pintype "bidirectional"))
      (node (ref "RS232") (pin "P$11") (pinfunction "D-_P$11") (pintype "bidirectional"))
      (node (ref "U$21") (pin "P$1") (pinfunction "LB_P$1") (pintype "bidirectional"))
      (node (ref "U$21") (pin "P$3") (pinfunction "RB_P$3") (pintype "bidirectional"))
    )
    (net (code "12") (name "CONTACTOR_CONTROL") (class "Default")
      (node (ref "CONT1") (pin "P$9") (pinfunction "A1_P$9") (pintype "bidirectional"))
      (node (ref "RELAY2") (pin "P$1") (pinfunction "11_P$1") (pintype "bidirectional"))
    )
    (net (code "13") (name "DC_COMMON") (class "Default")
      (node (ref "CPU1") (pin "P$J12-1") (pinfunction "J12_1_AGND_P$J12-1") (pintype "bidirectional"))
      (node (ref "CPU1") (pin "P$J5-3") (pinfunction "J5_3_GND_P$J5-3") (pintype "bidirectional"))
      (node (ref "DISPLAY1") (pin "P$4") (pinfunction "GND_B_P$4") (pintype "bidirectional"))
      (node (ref "HALL") (pin "P$2") (pinfunction "GND(BK)_P$2") (pintype "bidirectional"))
      (node (ref "JOYSTICK") (pin "P$3") (pinfunction "GND_P$3") (pintype "bidirectional"))
      (node (ref "LAMP1") (pin "P$2") (pinfunction "P$6_P$2") (pintype "bidirectional"))
      (node (ref "PS1") (pin "P$4") (pinfunction "4-(V-)_P$4") (pintype "bidirectional"))
      (node (ref "PS2") (pin "P$4") (pinfunction "GND1_P$4") (pintype "bidirectional"))
      (node (ref "PS2") (pin "P$5") (pinfunction "GND2_P$5") (pintype "bidirectional"))
      (node (ref "R2") (pin "P$1") (pinfunction "1_P$1") (pintype "passive"))
      (node (ref "RADIO1") (pin "P$53") (pinfunction "GND_P$53") (pintype "bidirectional"))
      (node (ref "RELAY1") (pin "P$5") (pinfunction "A2_P$5") (pintype "bidirectional"))
      (node (ref "RELAY2") (pin "P$5") (pinfunction "A2_P$5") (pintype "bidirectional"))
      (node (ref "REMOTE") (pin "P$6") (pinfunction "P$6_P$6") (pintype "bidirectional"))
      (node (ref "RS232") (pin "P$12") (pinfunction "GND_P$12") (pintype "bidirectional"))
      (node (ref "SPEED") (pin "P$6") (pinfunction "P$6_P$6") (pintype "bidirectional"))
      (node (ref "U$26") (pin "P$3") (pinfunction "RB_P$3") (pintype "bidirectional"))
      (node (ref "U$27") (pin "P$1") (pinfunction "LB_P$1") (pintype "bidirectional"))
      (node (ref "U$27") (pin "P$3") (pinfunction "RB_P$3") (pintype "bidirectional"))
      (node (ref "U$28") (pin "P$1") (pinfunction "LB_P$1") (pintype "bidirectional"))
      (node (ref "U$29") (pin "P$3") (pinfunction "RB_P$3") (pintype "bidirectional"))
      (node (ref "U$3") (pin "P$6") (pinfunction "P$6_P$6") (pintype "bidirectional"))
      (node (ref "U$30") (pin "P$3") (pinfunction "RB_P$3") (pintype "bidirectional"))
      (node (ref "U$31") (pin "P$1") (pinfunction "LB_P$1") (pintype "bidirectional"))
      (node (ref "U$31") (pin "P$3") (pinfunction "RB_P$3") (pintype "bidirectional"))
      (node (ref "U$32") (pin "P$1") (pinfunction "LB_P$1") (pintype "bidirectional"))
      (node (ref "U$32") (pin "P$3") (pinfunction "RB_P$3") (pintype "bidirectional"))
      (node (ref "U$33") (pin "P$3") (pinfunction "RB_P$3") (pintype "bidirectional"))
      (node (ref "U$34") (pin "P$1") (pinfunction "LB_P$1") (pintype "bidirectional"))
      (node (ref "U$35") (pin "P$1") (pinfunction "LB_P$1") (pintype "bidirectional"))
      (node (ref "U$8") (pin "P$3") (pinfunction "RB_P$3") (pintype "bidirectional"))
      (node (ref "VFD1") (pin "P$18") (pinfunction "P$18_P$18") (pintype "bidirectional"))
      (node (ref "VFD1") (pin "P$9") (pinfunction "P$9_P$9") (pintype "bidirectional"))
      (node (ref "VFD2") (pin "P$7") (pinfunction "P$7_P$7") (pintype "bidirectional"))
    )
    (net (code "14") (name "DISPLAY_RS232_RX") (class "Default")
      (node (ref "DISPLAY1") (pin "P$5") (pinfunction "RS232_TX_P$5") (pintype "bidirectional"))
      (node (ref "U$19") (pin "P$4") (pinfunction "RT_P$4") (pintype "bidirectional"))
    )
    (net (code "15") (name "DISPLAY_RS232_TX") (class "Default")
      (node (ref "CPU1") (pin "P$J11-1") (pinfunction "J11_1_PD6_TXE_P$J11-1") (pintype "bidirectional"))
      (node (ref "U$19") (pin "P$2") (pinfunction "LT_P$2") (pintype "bidirectional"))
    )
    (net (code "16") (name "DRIVE_24VDC") (class "Default")
      (node (ref "CPU1") (pin "P$J3-10") (pinfunction "J3_10_+K1_P$J3-10") (pintype "bidirectional"))
      (node (ref "U$27") (pin "P$2") (pinfunction "LT_P$2") (pintype "bidirectional"))
      (node (ref "U$27") (pin "P$4") (pinfunction "RT_P$4") (pintype "bidirectional"))
      (node (ref "VFD1") (pin "P$11") (pinfunction "P$11_P$11") (pintype "bidirectional"))
    )
    (net (code "17") (name "DRIVE_ALARM") (class "Default")
      (node (ref "CPU1") (pin "P$J1-9") (pinfunction "J1_9_DIO16_P$J1-9") (pintype "bidirectional"))
      (node (ref "U$23") (pin "P$2") (pinfunction "LT_P$2") (pintype "bidirectional"))
      (node (ref "U$23") (pin "P$4") (pinfunction "RT_P$4") (pintype "bidirectional"))
      (node (ref "VFD1") (pin "P$22") (pinfunction "P$22_P$22") (pintype "bidirectional"))
    )
    (net (code "18") (name "DRIVE_FWD") (class "Default")
      (node (ref "CPU1") (pin "P$J3-1") (pinfunction "J3_1_HOUT1_P$J3-1") (pintype "bidirectional"))
      (node (ref "U$22") (pin "P$2") (pinfunction "LT_P$2") (pintype "bidirectional"))
      (node (ref "U$22") (pin "P$4") (pinfunction "RT_P$4") (pintype "bidirectional"))
      (node (ref "VFD1") (pin "P$8") (pinfunction "P$8_P$8") (pintype "bidirectional"))
    )
    (net (code "19") (name "DRIVE_REV") (class "Default")
      (node (ref "CPU1") (pin "P$J3-4") (pinfunction "J3_4_HOUT3_P$J3-4") (pintype "bidirectional"))
      (node (ref "U$22") (pin "P$1") (pinfunction "LB_P$1") (pintype "bidirectional"))
      (node (ref "U$22") (pin "P$3") (pinfunction "RB_P$3") (pintype "bidirectional"))
      (node (ref "VFD1") (pin "P$7") (pinfunction "P$7_P$7") (pintype "bidirectional"))
    )
    (net (code "20") (name "DRIVE_SIGNAL") (class "Default")
      (node (ref "CPU1") (pin "P$J12-13") (pinfunction "J12_13_AOUT0_P$J12-13") (pintype "bidirectional"))
      (node (ref "U$23") (pin "P$1") (pinfunction "LB_P$1") (pintype "bidirectional"))
      (node (ref "U$23") (pin "P$3") (pinfunction "RB_P$3") (pintype "bidirectional"))
      (node (ref "VFD1") (pin "P$16") (pinfunction "P$16_P$16") (pintype "bidirectional"))
    )
    (net (code "21") (name "ESTOP_SIGNAL") (class "Default")
      (node (ref "CPU1") (pin "P$J1-1") (pinfunction "J1_1_DIO23_P$J1-1") (pintype "bidirectional"))
      (node (ref "R2") (pin "P$2") (pinfunction "2_P$2") (pintype "passive"))
      (node (ref "RELAY2") (pin "P$4") (pinfunction "A1_P$4") (pintype "bidirectional"))
      (node (ref "U$3") (pin "P$3") (pinfunction "P$3_P$3") (pintype "bidirectional"))
      (node (ref "U$3") (pin "P$4") (pinfunction "P$4_P$4") (pintype "bidirectional"))
      (node (ref "U$3") (pin "P$5") (pinfunction "P$5_P$5") (pintype "bidirectional"))
      (node (ref "U$4") (pin "P$2") (pinfunction "LT_P$2") (pintype "bidirectional"))
      (node (ref "U$4") (pin "P$4") (pinfunction "RT_P$4") (pintype "bidirectional"))
    )
    (net (code "22") (name "HALL_EFFECT_SIGNAL") (class "Default")
      (node (ref "CPU1") (pin "P$J2-4") (pinfunction "J2_4_DIO25_P$J2-4") (pintype "bidirectional"))
      (node (ref "HALL") (pin "P$3") (pinfunction "SIG(GN)_P$3") (pintype "bidirectional"))
      (node (ref "U$25") (pin "P$2") (pinfunction "LT_P$2") (pintype "bidirectional"))
      (node (ref "U$25") (pin "P$4") (pinfunction "RT_P$4") (pintype "bidirectional"))
    )
    (net (code "23") (name "HBU_N") (class "Default")
      (node (ref "VFD2") (pin "P$11") (pinfunction "P$11_P$11") (pintype "bidirectional"))
    )
    (net (code "24") (name "HBU_P") (class "Default")
      (node (ref "VFD2") (pin "P$10") (pinfunction "P$10_P$10") (pintype "bidirectional"))
    )
    (net (code "25") (name "HBU_P1") (class "Default")
      (node (ref "DBR1") (pin "2") (pinfunction "2_2") (pintype "passive"))
      (node (ref "DBR2") (pin "2") (pinfunction "2_2") (pintype "passive"))
      (node (ref "DBR3") (pin "2") (pinfunction "2_2") (pintype "passive"))
      (node (ref "VFD2") (pin "P$8") (pinfunction "P$8_P$8") (pintype "bidirectional"))
    )
    (net (code "26") (name "HBU_P2") (class "Default")
      (node (ref "DBR1") (pin "1") (pinfunction "1_1") (pintype "passive"))
      (node (ref "DBR2") (pin "1") (pinfunction "1_1") (pintype "passive"))
      (node (ref "DBR3") (pin "1") (pinfunction "1_1") (pintype "passive"))
      (node (ref "VFD2") (pin "P$9") (pinfunction "P$9_P$9") (pintype "bidirectional"))
    )
    (net (code "27") (name "JOG_LEFT_SIGNAL") (class "Default")
      (node (ref "CPU1") (pin "P$J1-3") (pinfunction "J1_3_DIO19_P$J1-3") (pintype "bidirectional"))
      (node (ref "U$1") (pin "P$2") (pinfunction "LT_P$2") (pintype "bidirectional"))
    )
    (net (code "28") (name "JOG_RIGHT_SIGNAL") (class "Default")
      (node (ref "CPU1") (pin "P$J1-4") (pinfunction "J1_4_DIO17_P$J1-4") (pintype "bidirectional"))
      (node (ref "U$1") (pin "P$1") (pinfunction "LB_P$1") (pintype "bidirectional"))
    )
    (net (code "29") (name "JOYSTICK_FORWARD_SIGNAL") (class "Default")
      (node (ref "CPU1") (pin "P$J1-7") (pinfunction "J1_7_DIO20_P$J1-7") (pintype "bidirectional"))
      (node (ref "JOYSTICK") (pin "P$2") (pinfunction "B_P$2") (pintype "bidirectional"))
      (node (ref "U$16") (pin "P$1") (pinfunction "LB_P$1") (pintype "bidirectional"))
      (node (ref "U$16") (pin "P$3") (pinfunction "RB_P$3") (pintype "bidirectional"))
    )
    (net (code "30") (name "JOYSTICK_REVERSE_SIGNAL") (class "Default")
      (node (ref "CPU1") (pin "P$J1-8") (pinfunction "J1_8_DIO18_P$J1-8") (pintype "bidirectional"))
      (node (ref "JOYSTICK") (pin "P$1") (pinfunction "A_P$1") (pintype "bidirectional"))
      (node (ref "U$17") (pin "P$1") (pinfunction "LB_P$1") (pintype "bidirectional"))
      (node (ref "U$17") (pin "P$3") (pinfunction "RB_P$3") (pintype "bidirectional"))
    )
    (net (code "31") (name "JOYSTICK_SIGNAL") (class "Default")
      (node (ref "CPU1") (pin "P$J12-12") (pinfunction "J12_12_AIN0_P$J12-12") (pintype "bidirectional"))
      (node (ref "JOYSTICK") (pin "P$4") (pinfunction "SIG_P$4") (pintype "bidirectional"))
      (node (ref "U$16") (pin "P$2") (pinfunction "LT_P$2") (pintype "bidirectional"))
      (node (ref "U$16") (pin "P$4") (pinfunction "RT_P$4") (pintype "bidirectional"))
    )
    (net (code "32") (name "MAINS_L1") (class "Default")
      (node (ref "DS") (pin "P$3") (pinfunction "P$3_P$3") (pintype "bidirectional"))
      (node (ref "DS") (pin "P$4") (pinfunction "P$4_P$4") (pintype "bidirectional"))
      (node (ref "FUSE1") (pin "P$2") (pinfunction "P$2_P$2") (pintype "bidirectional"))
    )
    (net (code "33") (name "MAINS_L1_FUSED") (class "Default")
      (node (ref "CONT1") (pin "P$1") (pinfunction "1L1_P$1") (pintype "bidirectional"))
      (node (ref "CONT1") (pin "P$2") (pinfunction "2T1_P$2") (pintype "bidirectional"))
      (node (ref "FUSE1") (pin "P$3") (pinfunction "P$3_P$3") (pintype "bidirectional"))
      (node (ref "PS1") (pin "P$1") (pinfunction "1-AC/L_P$1") (pintype "bidirectional"))
      (node (ref "RELAY1") (pin "P$3") (pinfunction "14_P$3") (pintype "bidirectional"))
      (node (ref "RELAY2") (pin "P$3") (pinfunction "14_P$3") (pintype "bidirectional"))
    )
    (net (code "34") (name "MAINS_L2") (class "Default")
      (node (ref "DS") (pin "P$2") (pinfunction "P$2_P$2") (pintype "bidirectional"))
      (node (ref "DS") (pin "P$5") (pinfunction "P$5_P$5") (pintype "bidirectional"))
      (node (ref "FUSE1") (pin "P$1") (pinfunction "P$1_P$1") (pintype "bidirectional"))
    )
    (net (code "35") (name "MAINS_L2_FUSED") (class "Default")
      (node (ref "CONT1") (pin "P$10") (pinfunction "A2_P$10") (pintype "bidirectional"))
      (node (ref "CONT1") (pin "P$4") (pinfunction "4T2_P$4") (pintype "bidirectional"))
      (node (ref "FUSE1") (pin "P$4") (pinfunction "P$4_P$4") (pintype "bidirectional"))
      (node (ref "PS1") (pin "P$2") (pinfunction "2-AC/N_P$2") (pintype "bidirectional"))
      (node (ref "U$6") (pin "P$3") (pinfunction "P$3_P$3") (pintype "bidirectional"))
    )
    (net (code "36") (name "MAINS_L3") (class "Default")
      (node (ref "DS") (pin "P$1") (pinfunction "P$1_P$1") (pintype "bidirectional"))
      (node (ref "DS") (pin "P$6") (pinfunction "P$6_P$6") (pintype "bidirectional"))
      (node (ref "FUSE1") (pin "P$5") (pinfunction "P$5_P$5") (pintype "bidirectional"))
    )
    (net (code "37") (name "MAINS_L3_FUSED") (class "Default")
      (node (ref "CONT1") (pin "P$5") (pinfunction "5L3_P$5") (pintype "bidirectional"))
      (node (ref "CONT1") (pin "P$6") (pinfunction "6T3_P$6") (pintype "bidirectional"))
      (node (ref "FUSE1") (pin "P$6") (pinfunction "P$6_P$6") (pintype "bidirectional"))
    )
    (net (code "38") (name "MAINS_PE") (class "Default")
      (node (ref "DS") (pin "P$7") (pinfunction "P$7_P$7") (pintype "bidirectional"))
      (node (ref "DS") (pin "P$8") (pinfunction "P$8_P$8") (pintype "bidirectional"))
    )
    (net (code "39") (name "MOTOR_PE") (class "Default")
      (node (ref "U$11") (pin "P$14") (pinfunction "GND_P$14") (pintype "bidirectional"))
    )
    (net (code "40") (name "MOTOR_U") (class "Default")
      (node (ref "U$11") (pin "P$11") (pinfunction "T7_P$11") (pintype "bidirectional"))
      (node (ref "U$11") (pin "P$5") (pinfunction "T1_P$5") (pintype "bidirectional"))
    )
    (net (code "41") (name "MOTOR_V") (class "Default")
      (node (ref "U$11") (pin "P$12") (pinfunction "T8_P$12") (pintype "bidirectional"))
      (node (ref "U$11") (pin "P$6") (pinfunction "T2_P$6") (pintype "bidirectional"))
    )
    (net (code "42") (name "MOTOR_W") (class "Default")
      (node (ref "U$11") (pin "P$13") (pinfunction "T9_P$13") (pintype "bidirectional"))
      (node (ref "U$11") (pin "P$7") (pinfunction "T3_P$7") (pintype "bidirectional"))
    )
    (net (code "43") (name "N$1") (class "Default")
      (node (ref "CPU1") (pin "P$J3-5") (pinfunction "J3_5_GND_P$J3-5") (pintype "bidirectional"))
    )
    (net (code "44") (name "N$2") (class "Default")
      (node (ref "U$7") (pin "P$3") (pinfunction "RB_P$3") (pintype "bidirectional"))
    )
    (net (code "45") (name "N$4") (class "Default")
      (node (ref "CONT1") (pin "P$3") (pinfunction "3L2_P$3") (pintype "bidirectional"))
    )
    (net (code "46") (name "Net-(LAMP1-P$5)") (class "Default")
      (node (ref "LAMP1") (pin "P$1") (pinfunction "P$5_P$1") (pintype "bidirectional"))
      (node (ref "REMOTE") (pin "P$1") (pinfunction "P$1_P$1") (pintype "bidirectional"))
    )
    (net (code "47") (name "Net-(U$8-LB)") (class "Default")
      (node (ref "R3") (pin "2") (pinfunction "2_2") (pintype "passive"))
      (node (ref "U$8") (pin "P$1") (pinfunction "LB_P$1") (pintype "bidirectional"))
    )
    (net (code "48") (name "Net-(U$11-T4)") (class "Default")
      (node (ref "U$11") (pin "P$10") (pinfunction "T6_P$10") (pintype "bidirectional"))
      (node (ref "U$11") (pin "P$8") (pinfunction "T4_P$8") (pintype "bidirectional"))
      (node (ref "U$11") (pin "P$9") (pinfunction "T5_P$9") (pintype "bidirectional"))
    )
    (net (code "49") (name "PE") (class "Default")
      (node (ref "PS1") (pin "P$3") (pinfunction "3-PE_P$3") (pintype "bidirectional"))
    )
    (net (code "50") (name "PROX_LEFT_SIGNAL") (class "Default")
      (node (ref "CPU1") (pin "P$J2-2") (pinfunction "J2_2_DIO29_P$J2-2") (pintype "bidirectional"))
      (node (ref "U$24") (pin "P$1") (pinfunction "LB_P$1") (pintype "bidirectional"))
    )
    (net (code "51") (name "PROX_RIGHT_SIGNAL") (class "Default")
      (node (ref "CPU1") (pin "P$J2-1") (pinfunction "J2_1_DIO31_P$J2-1") (pintype "bidirectional"))
      (node (ref "U$24") (pin "P$2") (pinfunction "LT_P$2") (pintype "bidirectional"))
    )
    (net (code "52") (name "RADIO_RS232_RX") (class "Default")
      (node (ref "CPU1") (pin "P$J11-7") (pinfunction "J11_7_PD3_RXF_P$J11-7") (pintype "bidirectional"))
      (node (ref "RADIO1") (pin "P$3") (pinfunction "P$3_P$3") (pintype "bidirectional"))
      (node (ref "U$20") (pin "P$1") (pinfunction "LB_P$1") (pintype "bidirectional"))
      (node (ref "U$20") (pin "P$3") (pinfunction "RB_P$3") (pintype "bidirectional"))
    )
    (net (code "53") (name "RADIO_RS232_TX") (class "Default")
      (node (ref "CPU1") (pin "P$J11-2") (pinfunction "J11_2_PD2_TXF_P$J11-2") (pintype "bidirectional"))
      (node (ref "RADIO1") (pin "P$2") (pinfunction "P$2_P$2") (pintype "bidirectional"))
      (node (ref "U$20") (pin "P$2") (pinfunction "LT_P$2") (pintype "bidirectional"))
      (node (ref "U$20") (pin "P$4") (pinfunction "RT_P$4") (pintype "bidirectional"))
    )
    (net (code "54") (name "REMOTE_SIGNAL") (class "Default")
      (node (ref "CPU1") (pin "P$J2-6") (pinfunction "J2_6_DIO30_P$J2-6") (pintype "bidirectional"))
      (node (ref "REMOTE") (pin "P$4") (pinfunction "P$4_P$4") (pintype "bidirectional"))
      (node (ref "U$17") (pin "P$2") (pinfunction "LT_P$2") (pintype "bidirectional"))
      (node (ref "U$17") (pin "P$4") (pinfunction "RT_P$4") (pintype "bidirectional"))
    )
    (net (code "55") (name "RESET_SIGNAL") (class "Default")
      (node (ref "CPU1") (pin "P$J1-6") (pinfunction "J1_6_DIO22_P$J1-6") (pintype "bidirectional"))
      (node (ref "RESET") (pin "P$1") (pinfunction "P$1_P$1") (pintype "bidirectional"))
      (node (ref "U$18") (pin "P$2") (pinfunction "LT_P$2") (pintype "bidirectional"))
      (node (ref "U$18") (pin "P$4") (pinfunction "RT_P$4") (pintype "bidirectional"))
    )
    (net (code "56") (name "SPEED_SIGNAL") (class "Default")
      (node (ref "CPU1") (pin "P$J2-7") (pinfunction "J2_7_DIO28_P$J2-7") (pintype "bidirectional"))
      (node (ref "SPEED") (pin "P$4") (pinfunction "P$4_P$4") (pintype "bidirectional"))
      (node (ref "U$18") (pin "P$1") (pinfunction "LB_P$1") (pintype "bidirectional"))
      (node (ref "U$18") (pin "P$3") (pinfunction "RB_P$3") (pintype "bidirectional"))
    )
    (net (code "57") (name "STEPPER_DIR") (class "Default")
      (node (ref "CPU1") (pin "P$J4-4") (pinfunction "J4_4_HOUT7_P$J4-4") (pintype "bidirectional"))
      (node (ref "U$2") (pin "P$1") (pinfunction "LB_P$1") (pintype "bidirectional"))
    )
    (net (code "58") (name "STEPPER_STEP") (class "Default")
      (node (ref "CPU1") (pin "P$J4-1") (pinfunction "J4_1_HOUT5_P$J4-1") (pintype "bidirectional"))
      (node (ref "U$2") (pin "P$2") (pinfunction "LT_P$2") (pintype "bidirectional"))
    )
    (net (code "59") (name "THERMISTOR_SIGNAL") (class "Default")
      (node (ref "CPU1") (pin "P$J12-2") (pinfunction "J12_2_AIN6_P$J12-2") (pintype "bidirectional"))
      (node (ref "R3") (pin "1") (pinfunction "1_1") (pintype "passive"))
      (node (ref "U$4") (pin "P$1") (pinfunction "LB_P$1") (pintype "bidirectional"))
      (node (ref "U$4") (pin "P$3") (pinfunction "RB_P$3") (pintype "bidirectional"))
      (node (ref "U$5") (pin "P$1") (pinfunction "P$1_P$1") (pintype "bidirectional"))
    )
    (net (code "60") (name "USER_INPUT_1") (class "Default")
      (node (ref "CPU1") (pin "P$J10-1") (pinfunction "J10_1_DIO7_P$J10-1") (pintype "bidirectional"))
    )
    (net (code "61") (name "USER_INPUT_2") (class "Default")
      (node (ref "CPU1") (pin "P$J10-2") (pinfunction "J10_2_DIO5_P$J10-2") (pintype "bidirectional"))
    )
    (net (code "62") (name "USER_INPUT_3") (class "Default")
      (node (ref "CPU1") (pin "P$J10-3") (pinfunction "J10_3_DIO3_P$J10-3") (pintype "bidirectional"))
    )
    (net (code "63") (name "USER_INPUT_4") (class "Default")
      (node (ref "CPU1") (pin "P$J10-4") (pinfunction "J10_4_DIO1_P$J10-4") (pintype "bidirectional"))
    )
    (net (code "64") (name "USER_INPUT_5") (class "Default")
      (node (ref "CPU1") (pin "P$J10-6") (pinfunction "J10_6_DIO6_P$J10-6") (pintype "bidirectional"))
    )
    (net (code "65") (name "unconnected-(CONT1-13NO-PadP$7)") (class "Default")
      (node (ref "CONT1") (pin "P$7") (pinfunction "13NO_P$7") (pintype "bidirectional"))
    )
    (net (code "66") (name "unconnected-(CONT1-14N0-PadP$8)") (class "Default")
      (node (ref "CONT1") (pin "P$8") (pinfunction "14N0_P$8") (pintype "bidirectional"))
    )
    (net (code "67") (name "unconnected-(CPU1-J1_2_DIO21-PadP$J1-2)") (class "Default")
      (node (ref "CPU1") (pin "P$J1-2") (pinfunction "J1_2_DIO21_P$J1-2") (pintype "bidirectional"))
    )
    (net (code "68") (name "unconnected-(CPU1-J1_5_GND-PadP$J1-5)") (class "Default")
      (node (ref "CPU1") (pin "P$J1-5") (pinfunction "J1_5_GND_P$J1-5") (pintype "bidirectional"))
    )
    (net (code "69") (name "unconnected-(CPU1-J1_10_+KC-PadP$J1-10)") (class "Default")
      (node (ref "CPU1") (pin "P$J1-10") (pinfunction "J1_10_+KC_P$J1-10") (pintype "bidirectional"))
    )
    (net (code "70") (name "unconnected-(CPU1-J2_3_DIO27-PadP$J2-3)") (class "Default")
      (node (ref "CPU1") (pin "P$J2-3") (pinfunction "J2_3_DIO27_P$J2-3") (pintype "bidirectional"))
    )
    (net (code "71") (name "unconnected-(CPU1-J2_5_GND-PadP$J2-5)") (class "Default")
      (node (ref "CPU1") (pin "P$J2-5") (pinfunction "J2_5_GND_P$J2-5") (pintype "bidirectional"))
    )
    (net (code "72") (name "unconnected-(CPU1-J2_8_DIO26-PadP$J2-8)") (class "Default")
      (node (ref "CPU1") (pin "P$J2-8") (pinfunction "J2_8_DIO26_P$J2-8") (pintype "bidirectional"))
    )
    (net (code "73") (name "unconnected-(CPU1-J2_9_DIO24-PadP$J2-9)") (class "Default")
      (node (ref "CPU1") (pin "P$J2-9") (pinfunction "J2_9_DIO24_P$J2-9") (pintype "bidirectional"))
    )
    (net (code "74") (name "unconnected-(CPU1-J2_10_+KD-PadP$J2-10)") (class "Default")
      (node (ref "CPU1") (pin "P$J2-10") (pinfunction "J2_10_+KD_P$J2-10") (pintype "bidirectional"))
    )
    (net (code "75") (name "unconnected-(CPU1-J3_2_GND-PadP$J3-2)") (class "Default")
      (node (ref "CPU1") (pin "P$J3-2") (pinfunction "J3_2_GND_P$J3-2") (pintype "bidirectional"))
    )
    (net (code "76") (name "unconnected-(CPU1-J3_6_HOUT0-PadP$J3-6)") (class "Default")
      (node (ref "CPU1") (pin "P$J3-6") (pinfunction "J3_6_HOUT0_P$J3-6") (pintype "bidirectional"))
    )
    (net (code "77") (name "unconnected-(CPU1-J3_7_+K1-PadP$J3-7)") (class "Default")
      (node (ref "CPU1") (pin "P$J3-7") (pinfunction "J3_7_+K1_P$J3-7") (pintype "bidirectional"))
    )
    (net (code "78") (name "unconnected-(CPU1-J3_9_HOUT2-PadP$J3-9)") (class "Default")
      (node (ref "CPU1") (pin "P$J3-9") (pinfunction "J3_9_HOUT2_P$J3-9") (pintype "bidirectional"))
    )
    (net (code "79") (name "unconnected-(CPU1-J4_2_GND-PadP$J4-2)") (class "Default")
      (node (ref "CPU1") (pin "P$J4-2") (pinfunction "J4_2_GND_P$J4-2") (pintype "bidirectional"))
    )
    (net (code "80") (name "unconnected-(CPU1-J4_5_GND-PadP$J4-5)") (class "Default")
      (node (ref "CPU1") (pin "P$J4-5") (pinfunction "J4_5_GND_P$J4-5") (pintype "bidirectional"))
    )
    (net (code "81") (name "unconnected-(CPU1-J4_6_HOUT4-PadP$J4-6)") (class "Default")
      (node (ref "CPU1") (pin "P$J4-6") (pinfunction "J4_6_HOUT4_P$J4-6") (pintype "bidirectional"))
    )
    (net (code "82") (name "unconnected-(CPU1-J4_7_+K2-PadP$J4-7)") (class "Default")
      (node (ref "CPU1") (pin "P$J4-7") (pinfunction "J4_7_+K2_P$J4-7") (pintype "bidirectional"))
    )
    (net (code "83") (name "unconnected-(CPU1-J4_9_HOUT6-PadP$J4-9)") (class "Default")
      (node (ref "CPU1") (pin "P$J4-9") (pinfunction "J4_9_HOUT6_P$J4-9") (pintype "bidirectional"))
    )
    (net (code "84") (name "unconnected-(CPU1-J7_1_+RAW-PadP$J7-1)") (class "Default")
      (node (ref "CPU1") (pin "P$J7-1") (pinfunction "J7_1_+RAW_P$J7-1") (pintype "bidirectional"))
    )
    (net (code "85") (name "unconnected-(CPU1-J7_2_+RAW-PadP$J7-2)") (class "Default")
      (node (ref "CPU1") (pin "P$J7-2") (pinfunction "J7_2_+RAW_P$J7-2") (pintype "bidirectional"))
    )
    (net (code "86") (name "unconnected-(CPU1-J7_3_+5V-PadP$J7-3)") (class "Default")
      (node (ref "CPU1") (pin "P$J7-3") (pinfunction "J7_3_+5V_P$J7-3") (pintype "bidirectional"))
    )
    (net (code "87") (name "unconnected-(CPU1-J7_4_GND-PadP$J7-4)") (class "Default")
      (node (ref "CPU1") (pin "P$J7-4") (pinfunction "J7_4_GND_P$J7-4") (pintype "bidirectional"))
    )
    (net (code "88") (name "unconnected-(CPU1-J7_5_GND-PadP$J7-5)") (class "Default")
      (node (ref "CPU1") (pin "P$J7-5") (pinfunction "J7_5_GND_P$J7-5") (pintype "bidirectional"))
    )
    (net (code "89") (name "unconnected-(CPU1-J7_6_+5V-PadP$J7-6)") (class "Default")
      (node (ref "CPU1") (pin "P$J7-6") (pinfunction "J7_6_+5V_P$J7-6") (pintype "bidirectional"))
    )
    (net (code "90") (name "unconnected-(CPU1-J9_1_DIO15-PadP$J9-1)") (class "Default")
      (node (ref "CPU1") (pin "P$J9-1") (pinfunction "J9_1_DIO15_P$J9-1") (pintype "bidirectional"))
    )
    (net (code "91") (name "unconnected-(CPU1-J9_2_DIO13-PadP$J9-2)") (class "Default")
      (node (ref "CPU1") (pin "P$J9-2") (pinfunction "J9_2_DIO13_P$J9-2") (pintype "bidirectional"))
    )
    (net (code "92") (name "unconnected-(CPU1-J9_3_DIO11-PadP$J9-3)") (class "Default")
      (node (ref "CPU1") (pin "P$J9-3") (pinfunction "J9_3_DIO11_P$J9-3") (pintype "bidirectional"))
    )
    (net (code "93") (name "unconnected-(CPU1-J9_4_DIO9-PadP$J9-4)") (class "Default")
      (node (ref "CPU1") (pin "P$J9-4") (pinfunction "J9_4_DIO9_P$J9-4") (pintype "bidirectional"))
    )
    (net (code "94") (name "unconnected-(CPU1-J9_5_GND-PadP$J9-5)") (class "Default")
      (node (ref "CPU1") (pin "P$J9-5") (pinfunction "J9_5_GND_P$J9-5") (pintype "bidirectional"))
    )
    (net (code "95") (name "unconnected-(CPU1-J9_6_DIO14-PadP$J9-6)") (class "Default")
      (node (ref "CPU1") (pin "P$J9-6") (pinfunction "J9_6_DIO14_P$J9-6") (pintype "bidirectional"))
    )
    (net (code "96") (name "unconnected-(CPU1-J9_7_DIO12-PadP$J9-7)") (class "Default")
      (node (ref "CPU1") (pin "P$J9-7") (pinfunction "J9_7_DIO12_P$J9-7") (pintype "bidirectional"))
    )
    (net (code "97") (name "unconnected-(CPU1-J9_8_DIO10-PadP$J9-8)") (class "Default")
      (node (ref "CPU1") (pin "P$J9-8") (pinfunction "J9_8_DIO10_P$J9-8") (pintype "bidirectional"))
    )
    (net (code "98") (name "unconnected-(CPU1-J9_9_DIO8-PadP$J9-9)") (class "Default")
      (node (ref "CPU1") (pin "P$J9-9") (pinfunction "J9_9_DIO8_P$J9-9") (pintype "bidirectional"))
    )
    (net (code "99") (name "unconnected-(CPU1-J9_10_+KB-PadP$J9-10)") (class "Default")
      (node (ref "CPU1") (pin "P$J9-10") (pinfunction "J9_10_+KB_P$J9-10") (pintype "bidirectional"))
    )
    (net (code "100") (name "unconnected-(CPU1-J10_5_GND-PadP$J10-5)") (class "Default")
      (node (ref "CPU1") (pin "P$J10-5") (pinfunction "J10_5_GND_P$J10-5") (pintype "bidirectional"))
    )
    (net (code "101") (name "unconnected-(CPU1-J10_7_DIO4-PadP$J10-7)") (class "Default")
      (node (ref "CPU1") (pin "P$J10-7") (pinfunction "J10_7_DIO4_P$J10-7") (pintype "bidirectional"))
    )
    (net (code "102") (name "unconnected-(CPU1-J10_8_DIO2-PadP$J10-8)") (class "Default")
      (node (ref "CPU1") (pin "P$J10-8") (pinfunction "J10_8_DIO2_P$J10-8") (pintype "bidirectional"))
    )
    (net (code "103") (name "unconnected-(CPU1-J10_9_DIO0-PadP$J10-9)") (class "Default")
      (node (ref "CPU1") (pin "P$J10-9") (pinfunction "J10_9_DIO0_P$J10-9") (pintype "bidirectional"))
    )
    (net (code "104") (name "unconnected-(CPU1-J10_10_+KA-PadP$J10-10)") (class "Default")
      (node (ref "CPU1") (pin "P$J10-10") (pinfunction "J10_10_+KA_P$J10-10") (pintype "bidirectional"))
    )
    (net (code "105") (name "unconnected-(CPU1-J11_3_GND-PadP$J11-3)") (class "Default")
      (node (ref "CPU1") (pin "P$J11-3") (pinfunction "J11_3_GND_P$J11-3") (pintype "bidirectional"))
    )
    (net (code "106") (name "unconnected-(CPU1-J11_5_GND-PadP$J11-5)") (class "Default")
      (node (ref "CPU1") (pin "P$J11-5") (pinfunction "J11_5_GND_P$J11-5") (pintype "bidirectional"))
    )
    (net (code "107") (name "unconnected-(CPU1-J11_6_PD7_RXE-PadP$J11-6)") (class "Default")
      (node (ref "CPU1") (pin "P$J11-6") (pinfunction "J11_6_PD7_RXE_P$J11-6") (pintype "bidirectional"))
    )
    (net (code "108") (name "unconnected-(CPU1-J11_8_GND-PadP$J11-8)") (class "Default")
      (node (ref "CPU1") (pin "P$J11-8") (pinfunction "J11_8_GND_P$J11-8") (pintype "bidirectional"))
    )
    (net (code "109") (name "unconnected-(CPU1-J12_3_AIN4-PadP$J12-3)") (class "Default")
      (node (ref "CPU1") (pin "P$J12-3") (pinfunction "J12_3_AIN4_P$J12-3") (pintype "bidirectional"))
    )
    (net (code "110") (name "unconnected-(CPU1-J12_4_AIN3-PadP$J12-4)") (class "Default")
      (node (ref "CPU1") (pin "P$J12-4") (pinfunction "J12_4_AIN3_P$J12-4") (pintype "bidirectional"))
    )
    (net (code "111") (name "unconnected-(CPU1-J12_5_AIN1-PadP$J12-5)") (class "Default")
      (node (ref "CPU1") (pin "P$J12-5") (pinfunction "J12_5_AIN1_P$J12-5") (pintype "bidirectional"))
    )
    (net (code "112") (name "unconnected-(CPU1-J12_6_AGND-PadP$J12-6)") (class "Default")
      (node (ref "CPU1") (pin "P$J12-6") (pinfunction "J12_6_AGND_P$J12-6") (pintype "bidirectional"))
    )
    (net (code "113") (name "unconnected-(CPU1-J12_7_AOUT1-PadP$J12-7)") (class "Default")
      (node (ref "CPU1") (pin "P$J12-7") (pinfunction "J12_7_AOUT1_P$J12-7") (pintype "bidirectional"))
    )
    (net (code "114") (name "unconnected-(CPU1-J12_8_AIN7-PadP$J12-8)") (class "Default")
      (node (ref "CPU1") (pin "P$J12-8") (pinfunction "J12_8_AIN7_P$J12-8") (pintype "bidirectional"))
    )
    (net (code "115") (name "unconnected-(CPU1-J12_9_AIN5-PadP$J12-9)") (class "Default")
      (node (ref "CPU1") (pin "P$J12-9") (pinfunction "J12_9_AIN5_P$J12-9") (pintype "bidirectional"))
    )
    (net (code "116") (name "unconnected-(CPU1-J12_10_AGND-PadP$J12-10)") (class "Default")
      (node (ref "CPU1") (pin "P$J12-10") (pinfunction "J12_10_AGND_P$J12-10") (pintype "bidirectional"))
    )
    (net (code "117") (name "unconnected-(CPU1-J12_11_AIN2-PadP$J12-11)") (class "Default")
      (node (ref "CPU1") (pin "P$J12-11") (pinfunction "J12_11_AIN2_P$J12-11") (pintype "bidirectional"))
    )
    (net (code "118") (name "unconnected-(CPU1-J12_14_AGND-PadP$J12-14)") (class "Default")
      (node (ref "CPU1") (pin "P$J12-14") (pinfunction "J12_14_AGND_P$J12-14") (pintype "bidirectional"))
    )
    (net (code "119") (name "unconnected-(DISPLAY1-5V_A-PadP$1)") (class "Default")
      (node (ref "DISPLAY1") (pin "P$1") (pinfunction "5V_A_P$1") (pintype "bidirectional"))
    )
    (net (code "120") (name "unconnected-(DISPLAY1-GND_A-PadP$3)") (class "Default")
      (node (ref "DISPLAY1") (pin "P$3") (pinfunction "GND_A_P$3") (pintype "bidirectional"))
    )
    (net (code "121") (name "unconnected-(PS2-+5VDCB-PadP$2)") (class "Default")
      (node (ref "PS2") (pin "P$2") (pinfunction "+5VDCB_P$2") (pintype "bidirectional"))
    )
    (net (code "122") (name "unconnected-(R1-Pad2)") (class "Default")
      (node (ref "R1") (pin "2") (pinfunction "2_2") (pintype "passive"))
    )
    (net (code "123") (name "unconnected-(RADIO1-PadP$1)") (class "Default")
      (node (ref "RADIO1") (pin "P$1") (pinfunction "P$1_P$1") (pintype "bidirectional"))
    )
    (net (code "124") (name "unconnected-(RADIO1-PadP$4)") (class "Default")
      (node (ref "RADIO1") (pin "P$4") (pinfunction "P$4_P$4") (pintype "bidirectional"))
    )
    (net (code "125") (name "unconnected-(RADIO1-PadP$5)") (class "Default")
      (node (ref "RADIO1") (pin "P$5") (pinfunction "P$5_P$5") (pintype "bidirectional"))
    )
    (net (code "126") (name "unconnected-(RADIO1-PadP$6)") (class "Default")
      (node (ref "RADIO1") (pin "P$6") (pinfunction "P$6_P$6") (pintype "bidirectional"))
    )
    (net (code "127") (name "unconnected-(RADIO1-PadP$7)") (class "Default")
      (node (ref "RADIO1") (pin "P$7") (pinfunction "P$7_P$7") (pintype "bidirectional"))
    )
    (net (code "128") (name "unconnected-(RADIO1-PadP$8)") (class "Default")
      (node (ref "RADIO1") (pin "P$8") (pinfunction "P$8_P$8") (pintype "bidirectional"))
    )
    (net (code "129") (name "unconnected-(RADIO1-PadP$9)") (class "Default")
      (node (ref "RADIO1") (pin "P$9") (pinfunction "P$9_P$9") (pintype "bidirectional"))
    )
    (net (code "130") (name "unconnected-(RADIO1-PadP$10)") (class "Default")
      (node (ref "RADIO1") (pin "P$10") (pinfunction "P$10_P$10") (pintype "bidirectional"))
    )
    (net (code "131") (name "unconnected-(RADIO1-PadP$11)") (class "Default")
      (node (ref "RADIO1") (pin "P$11") (pinfunction "P$11_P$11") (pintype "bidirectional"))
    )
    (net (code "132") (name "unconnected-(RADIO1-PadP$12)") (class "Default")
      (node (ref "RADIO1") (pin "P$12") (pinfunction "P$12_P$12") (pintype "bidirectional"))
    )
    (net (code "133") (name "unconnected-(RADIO1-PadP$13)") (class "Default")
      (node (ref "RADIO1") (pin "P$13") (pinfunction "P$13_P$13") (pintype "bidirectional"))
    )
    (net (code "134") (name "unconnected-(RADIO1-PadP$14)") (class "Default")
      (node (ref "RADIO1") (pin "P$14") (pinfunction "P$14_P$14") (pintype "bidirectional"))
    )
    (net (code "135") (name "unconnected-(RADIO1-PadP$15)") (class "Default")
      (node (ref "RADIO1") (pin "P$15") (pinfunction "P$15_P$15") (pintype "bidirectional"))
    )
    (net (code "136") (name "unconnected-(RADIO1-PadP$16)") (class "Default")
      (node (ref "RADIO1") (pin "P$16") (pinfunction "P$16_P$16") (pintype "bidirectional"))
    )
    (net (code "137") (name "unconnected-(RADIO1-PadP$17)") (class "Default")
      (node (ref "RADIO1") (pin "P$17") (pinfunction "P$17_P$17") (pintype "bidirectional"))
    )
    (net (code "138") (name "unconnected-(RADIO1-PadP$18)") (class "Default")
      (node (ref "RADIO1") (pin "P$18") (pinfunction "P$18_P$18") (pintype "bidirectional"))
    )
    (net (code "139") (name "unconnected-(RADIO1-PadP$19)") (class "Default")
      (node (ref "RADIO1") (pin "P$19") (pinfunction "P$19_P$19") (pintype "bidirectional"))
    )
    (net (code "140") (name "unconnected-(RADIO1-PadP$20)") (class "Default")
      (node (ref "RADIO1") (pin "P$20") (pinfunction "P$20_P$20") (pintype "bidirectional"))
    )
    (net (code "141") (name "unconnected-(RADIO1-PadP$21)") (class "Default")
      (node (ref "RADIO1") (pin "P$21") (pinfunction "P$21_P$21") (pintype "bidirectional"))
    )
    (net (code "142") (name "unconnected-(RADIO1-PadP$22)") (class "Default")
      (node (ref "RADIO1") (pin "P$22") (pinfunction "P$22_P$22") (pintype "bidirectional"))
    )
    (net (code "143") (name "unconnected-(RADIO1-PadP$23)") (class "Default")
      (node (ref "RADIO1") (pin "P$23") (pinfunction "P$23_P$23") (pintype "bidirectional"))
    )
    (net (code "144") (name "unconnected-(RADIO1-PadP$24)") (class "Default")
      (node (ref "RADIO1") (pin "P$24") (pinfunction "P$24_P$24") (pintype "bidirectional"))
    )
    (net (code "145") (name "unconnected-(RADIO1-PadP$25)") (class "Default")
      (node (ref "RADIO1") (pin "P$25") (pinfunction "P$25_P$25") (pintype "bidirectional"))
    )
    (net (code "146") (name "unconnected-(RADIO1-PadP$26)") (class "Default")
      (node (ref "RADIO1") (pin "P$26") (pinfunction "P$26_P$26") (pintype "bidirectional"))
    )
    (net (code "147") (name "unconnected-(RADIO1-PadP$27)") (class "Default")
      (node (ref "RADIO1") (pin "P$27") (pinfunction "P$27_P$27") (pintype "bidirectional"))
    )
    (net (code "148") (name "unconnected-(RADIO1-PadP$28)") (class "Default")
      (node (ref "RADIO1") (pin "P$28") (pinfunction "P$28_P$28") (pintype "bidirectional"))
    )
    (net (code "149") (name "unconnected-(RADIO1-PadP$29)") (class "Default")
      (node (ref "RADIO1") (pin "P$29") (pinfunction "P$29_P$29") (pintype "bidirectional"))
    )
    (net (code "150") (name "unconnected-(RADIO1-PadP$30)") (class "Default")
      (node (ref "RADIO1") (pin "P$30") (pinfunction "P$30_P$30") (pintype "bidirectional"))
    )
    (net (code "151") (name "unconnected-(RADIO1-PadP$31)") (class "Default")
      (node (ref "RADIO1") (pin "P$31") (pinfunction "P$31_P$31") (pintype "bidirectional"))
    )
    (net (code "152") (name "unconnected-(RADIO1-PadP$32)") (class "Default")
      (node (ref "RADIO1") (pin "P$32") (pinfunction "P$32_P$32") (pintype "bidirectional"))
    )
    (net (code "153") (name "unconnected-(RADIO1-PadP$33)") (class "Default")
      (node (ref "RADIO1") (pin "P$33") (pinfunction "P$33_P$33") (pintype "bidirectional"))
    )
    (net (code "154") (name "unconnected-(RADIO1-PadP$34)") (class "Default")
      (node (ref "RADIO1") (pin "P$34") (pinfunction "P$34_P$34") (pintype "bidirectional"))
    )
    (net (code "155") (name "unconnected-(RADIO1-PadP$35)") (class "Default")
      (node (ref "RADIO1") (pin "P$35") (pinfunction "P$35_P$35") (pintype "bidirectional"))
    )
    (net (code "156") (name "unconnected-(RADIO1-PadP$36)") (class "Default")
      (node (ref "RADIO1") (pin "P$36") (pinfunction "P$36_P$36") (pintype "bidirectional"))
    )
    (net (code "157") (name "unconnected-(RADIO1-PadP$37)") (class "Default")
      (node (ref "RADIO1") (pin "P$37") (pinfunction "P$37_P$37") (pintype "bidirectional"))
    )
    (net (code "158") (name "unconnected-(RADIO1-PadP$38)") (class "Default")
      (node (ref "RADIO1") (pin "P$38") (pinfunction "P$38_P$38") (pintype "bidirectional"))
    )
    (net (code "159") (name "unconnected-(RADIO1-PadP$39)") (class "Default")
      (node (ref "RADIO1") (pin "P$39") (pinfunction "P$39_P$39") (pintype "bidirectional"))
    )
    (net (code "160") (name "unconnected-(RADIO1-PadP$40)") (class "Default")
      (node (ref "RADIO1") (pin "P$40") (pinfunction "P$40_P$40") (pintype "bidirectional"))
    )
    (net (code "161") (name "unconnected-(RADIO1-PadP$41)") (class "Default")
      (node (ref "RADIO1") (pin "P$41") (pinfunction "P$41_P$41") (pintype "bidirectional"))
    )
    (net (code "162") (name "unconnected-(RADIO1-PadP$42)") (class "Default")
      (node (ref "RADIO1") (pin "P$42") (pinfunction "P$42_P$42") (pintype "bidirectional"))
    )
    (net (code "163") (name "unconnected-(RADIO1-PadP$43)") (class "Default")
      (node (ref "RADIO1") (pin "P$43") (pinfunction "P$43_P$43") (pintype "bidirectional"))
    )
    (net (code "164") (name "unconnected-(RADIO1-PadP$44)") (class "Default")
      (node (ref "RADIO1") (pin "P$44") (pinfunction "P$44_P$44") (pintype "bidirectional"))
    )
    (net (code "165") (name "unconnected-(RADIO1-PadP$45)") (class "Default")
      (node (ref "RADIO1") (pin "P$45") (pinfunction "P$45_P$45") (pintype "bidirectional"))
    )
    (net (code "166") (name "unconnected-(RADIO1-PadP$46)") (class "Default")
      (node (ref "RADIO1") (pin "P$46") (pinfunction "P$46_P$46") (pintype "bidirectional"))
    )
    (net (code "167") (name "unconnected-(RADIO1-PadP$47)") (class "Default")
      (node (ref "RADIO1") (pin "P$47") (pinfunction "P$47_P$47") (pintype "bidirectional"))
    )
    (net (code "168") (name "unconnected-(RADIO1-PadP$48)") (class "Default")
      (node (ref "RADIO1") (pin "P$48") (pinfunction "P$48_P$48") (pintype "bidirectional"))
    )
    (net (code "169") (name "unconnected-(RADIO1-PadP$49)") (class "Default")
      (node (ref "RADIO1") (pin "P$49") (pinfunction "P$49_P$49") (pintype "bidirectional"))
    )
    (net (code "170") (name "unconnected-(RADIO1-PadP$50)") (class "Default")
      (node (ref "RADIO1") (pin "P$50") (pinfunction "P$50_P$50") (pintype "bidirectional"))
    )
    (net (code "171") (name "unconnected-(RADIO1-PadP$51)") (class "Default")
      (node (ref "RADIO1") (pin "P$51") (pinfunction "P$51_P$51") (pintype "bidirectional"))
    )
    (net (code "172") (name "unconnected-(RELAY1-12-PadP$2)") (class "Default")
      (node (ref "RELAY1") (pin "P$2") (pinfunction "12_P$2") (pintype "bidirectional"))
    )
    (net (code "173") (name "unconnected-(RELAY2-12-PadP$2)") (class "Default")
      (node (ref "RELAY2") (pin "P$2") (pinfunction "12_P$2") (pintype "bidirectional"))
    )
    (net (code "174") (name "unconnected-(REMOTE-PadP$3)") (class "Default")
      (node (ref "REMOTE") (pin "P$3") (pinfunction "P$3_P$3") (pintype "bidirectional"))
    )
    (net (code "175") (name "unconnected-(RS232-1-PadP$1)") (class "Default")
      (node (ref "RS232") (pin "P$1") (pinfunction "1_P$1") (pintype "bidirectional"))
    )
    (net (code "176") (name "unconnected-(RS232-2-PadP$2)") (class "Default")
      (node (ref "RS232") (pin "P$2") (pinfunction "2_P$2") (pintype "bidirectional"))
    )
    (net (code "177") (name "unconnected-(RS232-3-PadP$3)") (class "Default")
      (node (ref "RS232") (pin "P$3") (pinfunction "3_P$3") (pintype "bidirectional"))
    )
    (net (code "178") (name "unconnected-(RS232-4-PadP$4)") (class "Default")
      (node (ref "RS232") (pin "P$4") (pinfunction "4_P$4") (pintype "bidirectional"))
    )
    (net (code "179") (name "unconnected-(RS232-5-PadP$5)") (class "Default")
      (node (ref "RS232") (pin "P$5") (pinfunction "5_P$5") (pintype "bidirectional"))
    )
    (net (code "180") (name "unconnected-(RS232-6-PadP$6)") (class "Default")
      (node (ref "RS232") (pin "P$6") (pinfunction "6_P$6") (pintype "bidirectional"))
    )
    (net (code "181") (name "unconnected-(RS232-7-PadP$7)") (class "Default")
      (node (ref "RS232") (pin "P$7") (pinfunction "7_P$7") (pintype "bidirectional"))
    )
    (net (code "182") (name "unconnected-(RS232-8-PadP$8)") (class "Default")
      (node (ref "RS232") (pin "P$8") (pinfunction "8_P$8") (pintype "bidirectional"))
    )
    (net (code "183") (name "unconnected-(RS232-9-PadP$9)") (class "Default")
      (node (ref "RS232") (pin "P$9") (pinfunction "9_P$9") (pintype "bidirectional"))
    )
    (net (code "184") (name "unconnected-(SPEED-PadP$1)") (class "Default")
      (node (ref "SPEED") (pin "P$1") (pinfunction "P$1_P$1") (pintype "bidirectional"))
    )
    (net (code "185") (name "unconnected-(SPEED-PadP$2)") (class "Default")
      (node (ref "SPEED") (pin "P$2") (pinfunction "P$2_P$2") (pintype "bidirectional"))
    )
    (net (code "186") (name "unconnected-(SPEED-PadP$3)") (class "Default")
      (node (ref "SPEED") (pin "P$3") (pinfunction "P$3_P$3") (pintype "bidirectional"))
    )
    (net (code "187") (name "unconnected-(U$1-RB-PadP$3)") (class "Default")
      (node (ref "U$1") (pin "P$3") (pinfunction "RB_P$3") (pintype "bidirectional"))
    )
    (net (code "188") (name "unconnected-(U$1-RT-PadP$4)") (class "Default")
      (node (ref "U$1") (pin "P$4") (pinfunction "RT_P$4") (pintype "bidirectional"))
    )
    (net (code "189") (name "unconnected-(U$2-RB-PadP$3)") (class "Default")
      (node (ref "U$2") (pin "P$3") (pinfunction "RB_P$3") (pintype "bidirectional"))
    )
    (net (code "190") (name "unconnected-(U$2-RT-PadP$4)") (class "Default")
      (node (ref "U$2") (pin "P$4") (pinfunction "RT_P$4") (pintype "bidirectional"))
    )
    (net (code "191") (name "unconnected-(U$7-LB-PadP$1)") (class "Default")
      (node (ref "U$7") (pin "P$1") (pinfunction "LB_P$1") (pintype "bidirectional"))
    )
    (net (code "192") (name "unconnected-(U$7-LT-PadP$2)") (class "Default")
      (node (ref "U$7") (pin "P$2") (pinfunction "LT_P$2") (pintype "bidirectional"))
    )
    (net (code "193") (name "unconnected-(U$7-RT-PadP$4)") (class "Default")
      (node (ref "U$7") (pin "P$4") (pinfunction "RT_P$4") (pintype "bidirectional"))
    )
    (net (code "194") (name "unconnected-(U$8-LT-PadP$2)") (class "Default")
      (node (ref "U$8") (pin "P$2") (pinfunction "LT_P$2") (pintype "bidirectional"))
    )
    (net (code "195") (name "unconnected-(U$9-PadP$1)") (class "Default")
      (node (ref "U$9") (pin "P$1") (pinfunction "P$1_P$1") (pintype "bidirectional"))
    )
    (net (code "196") (name "unconnected-(U$9-PadP$3)") (class "Default")
      (node (ref "U$9") (pin "P$3") (pinfunction "P$3_P$3") (pintype "bidirectional"))
    )
    (net (code "197") (name "unconnected-(U$10-PadP$1)") (class "Default")
      (node (ref "U$10") (pin "P$1") (pinfunction "P$1_P$1") (pintype "bidirectional"))
    )
    (net (code "198") (name "unconnected-(U$10-PadP$3)") (class "Default")
      (node (ref "U$10") (pin "P$3") (pinfunction "P$3_P$3") (pintype "bidirectional"))
    )
    (net (code "199") (name "unconnected-(U$19-LB-PadP$1)") (class "Default")
      (node (ref "U$19") (pin "P$1") (pinfunction "LB_P$1") (pintype "bidirectional"))
    )
    (net (code "200") (name "unconnected-(U$19-RB-PadP$3)") (class "Default")
      (node (ref "U$19") (pin "P$3") (pinfunction "RB_P$3") (pintype "bidirectional"))
    )
    (net (code "201") (name "unconnected-(U$24-RB-PadP$3)") (class "Default")
      (node (ref "U$24") (pin "P$3") (pinfunction "RB_P$3") (pintype "bidirectional"))
    )
    (net (code "202") (name "unconnected-(U$24-RT-PadP$4)") (class "Default")
      (node (ref "U$24") (pin "P$4") (pinfunction "RT_P$4") (pintype "bidirectional"))
    )
    (net (code "203") (name "unconnected-(U$25-LB-PadP$1)") (class "Default")
      (node (ref "U$25") (pin "P$1") (pinfunction "LB_P$1") (pintype "bidirectional"))
    )
    (net (code "204") (name "unconnected-(U$25-RB-PadP$3)") (class "Default")
      (node (ref "U$25") (pin "P$3") (pinfunction "RB_P$3") (pintype "bidirectional"))
    )
    (net (code "205") (name "unconnected-(U$26-LB-PadP$1)") (class "Default")
      (node (ref "U$26") (pin "P$1") (pinfunction "LB_P$1") (pintype "bidirectional"))
    )
    (net (code "206") (name "unconnected-(U$26-RT-PadP$4)") (class "Default")
      (node (ref "U$26") (pin "P$4") (pinfunction "RT_P$4") (pintype "bidirectional"))
    )
    (net (code "207") (name "unconnected-(U$28-RB-PadP$3)") (class "Default")
      (node (ref "U$28") (pin "P$3") (pinfunction "RB_P$3") (pintype "bidirectional"))
    )
    (net (code "208") (name "unconnected-(U$28-RT-PadP$4)") (class "Default")
      (node (ref "U$28") (pin "P$4") (pinfunction "RT_P$4") (pintype "bidirectional"))
    )
    (net (code "209") (name "unconnected-(U$29-LB-PadP$1)") (class "Default")
      (node (ref "U$29") (pin "P$1") (pinfunction "LB_P$1") (pintype "bidirectional"))
    )
    (net (code "210") (name "unconnected-(U$29-LT-PadP$2)") (class "Default")
      (node (ref "U$29") (pin "P$2") (pinfunction "LT_P$2") (pintype "bidirectional"))
    )
    (net (code "211") (name "unconnected-(U$30-LB-PadP$1)") (class "Default")
      (node (ref "U$30") (pin "P$1") (pinfunction "LB_P$1") (pintype "bidirectional"))
    )
    (net (code "212") (name "unconnected-(U$30-LT-PadP$2)") (class "Default")
      (node (ref "U$30") (pin "P$2") (pinfunction "LT_P$2") (pintype "bidirectional"))
    )
    (net (code "213") (name "unconnected-(U$33-LB-PadP$1)") (class "Default")
      (node (ref "U$33") (pin "P$1") (pinfunction "LB_P$1") (pintype "bidirectional"))
    )
    (net (code "214") (name "unconnected-(U$34-RB-PadP$3)") (class "Default")
      (node (ref "U$34") (pin "P$3") (pinfunction "RB_P$3") (pintype "bidirectional"))
    )
    (net (code "215") (name "unconnected-(U$34-RT-PadP$4)") (class "Default")
      (node (ref "U$34") (pin "P$4") (pinfunction "RT_P$4") (pintype "bidirectional"))
    )
    (net (code "216") (name "unconnected-(U$35-RB-PadP$3)") (class "Default")
      (node (ref "U$35") (pin "P$3") (pinfunction "RB_P$3") (pintype "bidirectional"))
    )
    (net (code "217") (name "unconnected-(VFD1-P$34-PadP$33)") (class "Default")
      (node (ref "VFD1") (pin "P$33") (pinfunction "P$34_P$33") (pintype "bidirectional"))
    )
    (net (code "218") (name "unconnected-(VFD1-P$35-PadP$34)") (class "Default")
      (node (ref "VFD1") (pin "P$34") (pinfunction "P$35_P$34") (pintype "bidirectional"))
    )
    (net (code "219") (name "unconnected-(VFD1-P$36-PadP$35)") (class "Default")
      (node (ref "VFD1") (pin "P$35") (pinfunction "P$36_P$35") (pintype "bidirectional"))
    )
    (net (code "220") (name "unconnected-(VFD1-PadP$1)") (class "Default")
      (node (ref "VFD1") (pin "P$1") (pinfunction "P$1_P$1") (pintype "bidirectional"))
    )
    (net (code "221") (name "unconnected-(VFD1-PadP$2)") (class "Default")
      (node (ref "VFD1") (pin "P$2") (pinfunction "P$2_P$2") (pintype "bidirectional"))
    )
    (net (code "222") (name "unconnected-(VFD1-PadP$3)") (class "Default")
      (node (ref "VFD1") (pin "P$3") (pinfunction "P$3_P$3") (pintype "bidirectional"))
    )
    (net (code "223") (name "unconnected-(VFD1-PadP$4)") (class "Default")
      (node (ref "VFD1") (pin "P$4") (pinfunction "P$4_P$4") (pintype "bidirectional"))
    )
    (net (code "224") (name "unconnected-(VFD1-PadP$5)") (class "Default")
      (node (ref "VFD1") (pin "P$5") (pinfunction "P$5_P$5") (pintype "bidirectional"))
    )
    (net (code "225") (name "unconnected-(VFD1-PadP$6)") (class "Default")
      (node (ref "VFD1") (pin "P$6") (pinfunction "P$6_P$6") (pintype "bidirectional"))
    )
    (net (code "226") (name "unconnected-(VFD1-PadP$10)") (class "Default")
      (node (ref "VFD1") (pin "P$10") (pinfunction "P$10_P$10") (pintype "bidirectional"))
    )
    (net (code "227") (name "unconnected-(VFD1-PadP$12)") (class "Default")
      (node (ref "VFD1") (pin "P$12") (pinfunction "P$12_P$12") (pintype "bidirectional"))
    )
    (net (code "228") (name "unconnected-(VFD1-PadP$13)") (class "Default")
      (node (ref "VFD1") (pin "P$13") (pinfunction "P$13_P$13") (pintype "bidirectional"))
    )
    (net (code "229") (name "unconnected-(VFD1-PadP$14)") (class "Default")
      (node (ref "VFD1") (pin "P$14") (pinfunction "P$14_P$14") (pintype "bidirectional"))
    )
    (net (code "230") (name "unconnected-(VFD1-PadP$15)") (class "Default")
      (node (ref "VFD1") (pin "P$15") (pinfunction "P$15_P$15") (pintype "bidirectional"))
    )
    (net (code "231") (name "unconnected-(VFD1-PadP$17)") (class "Default")
      (node (ref "VFD1") (pin "P$17") (pinfunction "P$17_P$17") (pintype "bidirectional"))
    )
    (net (code "232") (name "unconnected-(VFD1-PadP$19)") (class "Default")
      (node (ref "VFD1") (pin "P$19") (pinfunction "P$19_P$19") (pintype "bidirectional"))
    )
    (net (code "233") (name "unconnected-(VFD1-PadP$20)") (class "Default")
      (node (ref "VFD1") (pin "P$20") (pinfunction "P$20_P$20") (pintype "bidirectional"))
    )
    (net (code "234") (name "unconnected-(VFD1-PadP$23)") (class "Default")
      (node (ref "VFD1") (pin "P$23") (pinfunction "P$23_P$23") (pintype "bidirectional"))
    )
    (net (code "235") (name "unconnected-(VFD1-PadP$24)") (class "Default")
      (node (ref "VFD1") (pin "P$24") (pinfunction "P$24_P$24") (pintype "bidirectional"))
    )
    (net (code "236") (name "unconnected-(VFD1-PadP$25)") (class "Default")
      (node (ref "VFD1") (pin "P$25") (pinfunction "P$25_P$25") (pintype "bidirectional"))
    )
    (net (code "237") (name "unconnected-(VFD1-PadP$26)") (class "Default")
      (node (ref "VFD1") (pin "P$26") (pinfunction "P$26_P$26") (pintype "bidirectional"))
    )
    (net (code "238") (name "unconnected-(VFD1-PadP$27)") (class "Default")
      (node (ref "VFD1") (pin "P$27") (pinfunction "P$27_P$27") (pintype "bidirectional"))
    )
    (net (code "239") (name "unconnected-(VFD1-PadP$28)") (class "Default")
      (node (ref "VFD1") (pin "P$28") (pinfunction "P$28_P$28") (pintype "bidirectional"))
    )
    (net (code "240") (name "unconnected-(VFD1-PadP$29)") (class "Default")
      (node (ref "VFD1") (pin "P$29") (pinfunction "P$29_P$29") (pintype "bidirectional"))
    )
    (net (code "241") (name "unconnected-(VFD1-PadP$30)") (class "Default")
      (node (ref "VFD1") (pin "P$30") (pinfunction "P$30_P$30") (pintype "bidirectional"))
    )
    (net (code "242") (name "unconnected-(VFD1-PadP$31)") (class "Default")
      (node (ref "VFD1") (pin "P$31") (pinfunction "P$31_P$31") (pintype "bidirectional"))
    )
    (net (code "243") (name "unconnected-(VFD1-PadP$32)") (class "Default")
      (node (ref "VFD1") (pin "P$32") (pinfunction "P$32_P$32") (pintype "bidirectional"))
    )
    (net (code "244") (name "unconnected-(VFD2-PadP$1)") (class "Default")
      (node (ref "VFD2") (pin "P$1") (pinfunction "P$1_P$1") (pintype "bidirectional"))
    )
    (net (code "245") (name "unconnected-(VFD2-PadP$2)") (class "Default")
      (node (ref "VFD2") (pin "P$2") (pinfunction "P$2_P$2") (pintype "bidirectional"))
    )
    (net (code "246") (name "unconnected-(VFD2-PadP$3)") (class "Default")
      (node (ref "VFD2") (pin "P$3") (pinfunction "P$3_P$3") (pintype "bidirectional"))
    )
    (net (code "247") (name "unconnected-(VFD2-PadP$4)") (class "Default")
      (node (ref "VFD2") (pin "P$4") (pinfunction "P$4_P$4") (pintype "bidirectional"))
    )
    (net (code "248") (name "unconnected-(VFD2-PadP$5)") (class "Default")
      (node (ref "VFD2") (pin "P$5") (pinfunction "P$5_P$5") (pintype "bidirectional"))
    )
    (net (code "249") (name "unconnected-(VFD2-PadP$6)") (class "Default")
      (node (ref "VFD2") (pin "P$6") (pinfunction "P$6_P$6") (pintype "bidirectional"))
    )
  )
)
